# Nixie_Clock_v2.net
KiCad netlist of a schematic drawn in EAGLE
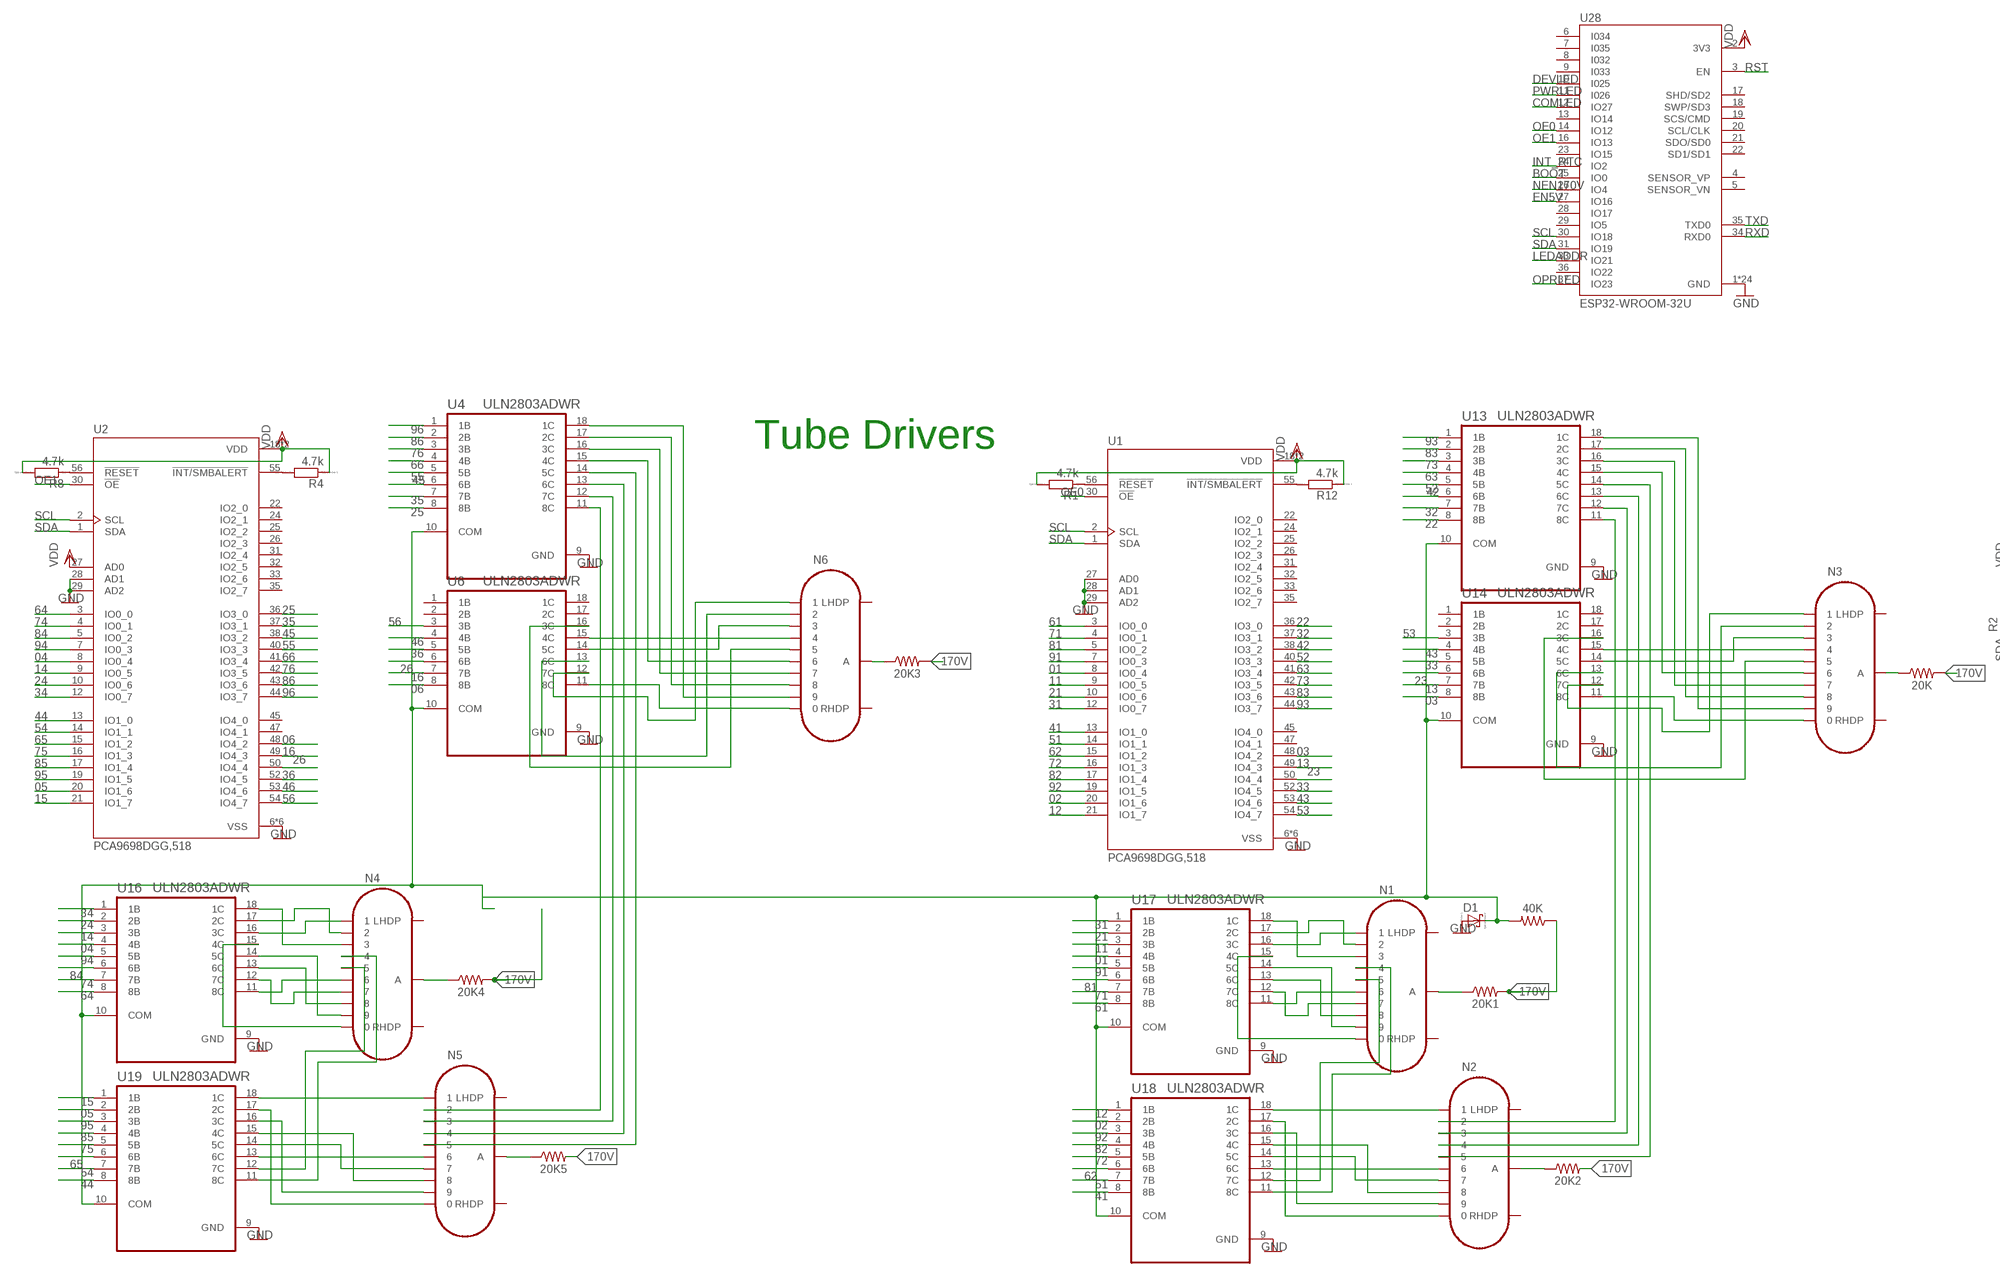
[diagram p0: schematic, sheet 1, part 1 of 2]
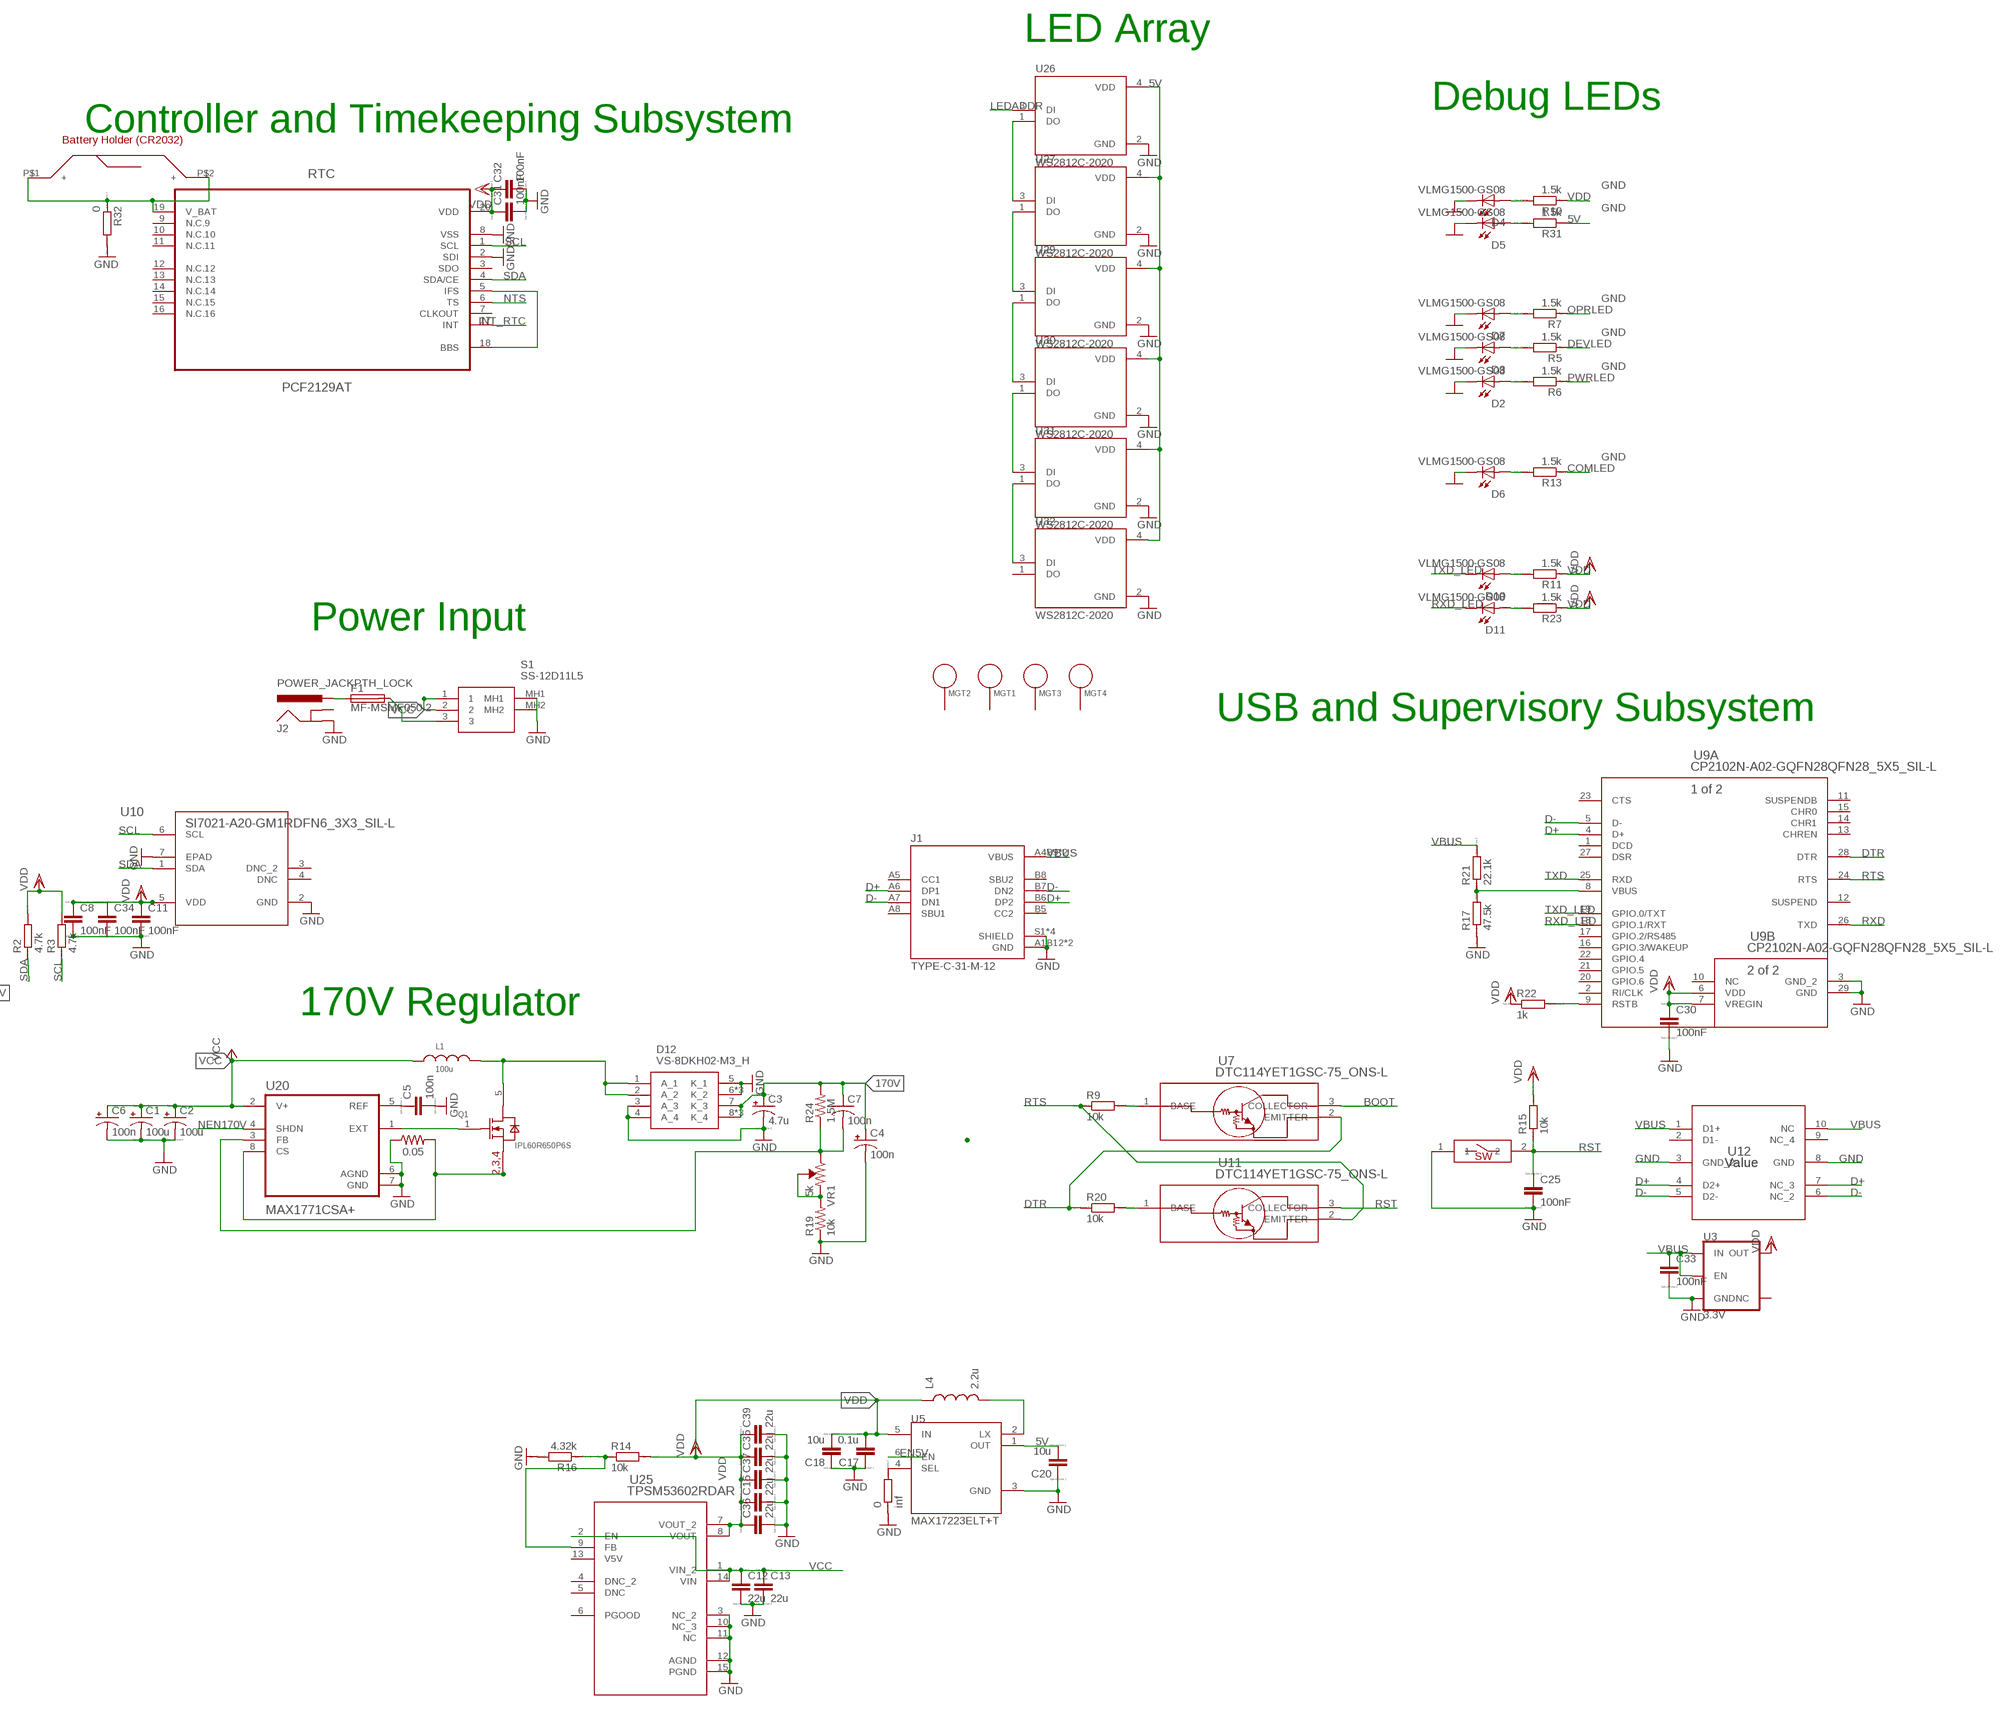
[diagram p1: schematic, sheet 1, part 2 of 2]

(export (version "E")
  (design (tool "Eeschema 10.0.6"))
  (components
    (comp (ref "0")
      (value "inf")
      (footprint "eagle-import:R0402")
      (libsource (lib "eagle-import") (part "RR0402"))
    )
    (comp (ref "0.05")
      (value "0.05")
      (footprint "eagle-import:1210")
      (libsource (lib "eagle-import") (part "0.1OHM-1210-1/2W-1%"))
    )
    (comp (ref "20K")
      (value "0.05")
      (footprint "eagle-import:1210")
      (libsource (lib "eagle-import") (part "0.1OHM-1210-1/2W-1%"))
    )
    (comp (ref "20K1")
      (value "0.05")
      (footprint "eagle-import:1210")
      (libsource (lib "eagle-import") (part "0.1OHM-1210-1/2W-1%"))
    )
    (comp (ref "20K2")
      (value "0.05")
      (footprint "eagle-import:1210")
      (libsource (lib "eagle-import") (part "0.1OHM-1210-1/2W-1%"))
    )
    (comp (ref "20K3")
      (value "0.05")
      (footprint "eagle-import:1210")
      (libsource (lib "eagle-import") (part "0.1OHM-1210-1/2W-1%"))
    )
    (comp (ref "20K4")
      (value "0.05")
      (footprint "eagle-import:1210")
      (libsource (lib "eagle-import") (part "0.1OHM-1210-1/2W-1%"))
    )
    (comp (ref "20K5")
      (value "0.05")
      (footprint "eagle-import:1210")
      (libsource (lib "eagle-import") (part "0.1OHM-1210-1/2W-1%"))
    )
    (comp (ref "40K")
      (value "0.05")
      (footprint "eagle-import:1210")
      (libsource (lib "eagle-import") (part "0.1OHM-1210-1/2W-1%"))
    )
    (comp (ref "C1")
      (value "100u")
      (footprint "eagle-import:E3,5-8")
      (libsource (lib "eagle-import") (part "CPOL-USE3.5-8"))
    )
    (comp (ref "C2")
      (value "100u")
      (footprint "eagle-import:E3,5-8")
      (libsource (lib "eagle-import") (part "CPOL-USE3.5-8"))
    )
    (comp (ref "C3")
      (value "4.7u")
      (footprint "eagle-import:E3,5-8")
      (libsource (lib "eagle-import") (part "CPOL-USE3.5-8"))
    )
    (comp (ref "C4")
      (value "100n")
      (footprint "eagle-import:A_3216-18W")
      (libsource (lib "eagle-import") (part "CAPACITOR-PA/3216-18W"))
    )
    (comp (ref "C5")
      (value "100n")
      (footprint "eagle-import:C0402")
      (libsource (lib "eagle-import") (part "CC0402"))
    )
    (comp (ref "C6")
      (value "100n")
      (footprint "eagle-import:A_3216-18W")
      (libsource (lib "eagle-import") (part "CAPACITOR-PA/3216-18W"))
    )
    (comp (ref "C7")
      (value "100n")
      (footprint "eagle-import:C1206K")
      (libsource (lib "eagle-import") (part "C-USC1206K"))
    )
    (comp (ref "C8")
      (value "100nF")
      (footprint "eagle-import:C0402")
      (libsource (lib "eagle-import") (part "CC0402"))
    )
    (comp (ref "C11")
      (value "100nF")
      (footprint "eagle-import:C0402")
      (libsource (lib "eagle-import") (part "CC0402"))
    )
    (comp (ref "C12")
      (value "22u")
      (footprint "eagle-import:C0603R")
      (libsource (lib "eagle-import") (part "CC0603R"))
    )
    (comp (ref "C13")
      (value "22u")
      (footprint "eagle-import:C0603R")
      (libsource (lib "eagle-import") (part "CC0603R"))
    )
    (comp (ref "C15")
      (value "22u")
      (footprint "eagle-import:C0603R")
      (libsource (lib "eagle-import") (part "CC0603R"))
    )
    (comp (ref "C17")
      (value "0.1u")
      (footprint "eagle-import:C0402")
      (libsource (lib "eagle-import") (part "CC0402"))
    )
    (comp (ref "C18")
      (value "10u")
      (footprint "eagle-import:C0402")
      (libsource (lib "eagle-import") (part "CC0402"))
    )
    (comp (ref "C20")
      (value "10u")
      (footprint "eagle-import:C0402")
      (libsource (lib "eagle-import") (part "CC0402"))
    )
    (comp (ref "C25")
      (value "100nF")
      (footprint "eagle-import:C0402")
      (libsource (lib "eagle-import") (part "CC0402"))
    )
    (comp (ref "C30")
      (value "100nF")
      (footprint "eagle-import:C0402")
      (libsource (lib "eagle-import") (part "CC0402"))
    )
    (comp (ref "C31")
      (value "100nF")
      (footprint "eagle-import:C0402")
      (libsource (lib "eagle-import") (part "CC0402"))
    )
    (comp (ref "C32")
      (value "100nF")
      (footprint "eagle-import:C0402")
      (libsource (lib "eagle-import") (part "CC0402"))
    )
    (comp (ref "C33")
      (value "100nF")
      (footprint "eagle-import:C0402")
      (libsource (lib "eagle-import") (part "CC0402"))
    )
    (comp (ref "C34")
      (value "100nF")
      (footprint "eagle-import:C0402")
      (libsource (lib "eagle-import") (part "CC0402"))
    )
    (comp (ref "C35")
      (value "22u")
      (footprint "eagle-import:C0603R")
      (libsource (lib "eagle-import") (part "CC0603R"))
    )
    (comp (ref "C36")
      (value "22u")
      (footprint "eagle-import:C0603R")
      (libsource (lib "eagle-import") (part "CC0603R"))
    )
    (comp (ref "C37")
      (value "22u")
      (footprint "eagle-import:C0603R")
      (libsource (lib "eagle-import") (part "CC0603R"))
    )
    (comp (ref "C39")
      (value "22u")
      (footprint "eagle-import:C0603R")
      (libsource (lib "eagle-import") (part "CC0603R"))
    )
    (comp (ref "D1")
      (value "SCHOTTKY-DIODE")
      (footprint "eagle-import:DIODE_SMB")
      (libsource (lib "eagle-import") (part "SCHOTTKY-DIODE"))
    )
    (comp (ref "D2")
      (value "VLMG1500-GS08")
      (footprint "eagle-import:LEDC1005X35N")
      (fields (field (name "MF") "Vishay"))
      (libsource (lib "eagle-import") (part "VLMG1500-GS08"))
    )
    (comp (ref "D3")
      (value "VLMG1500-GS08")
      (footprint "eagle-import:LEDC1005X35N")
      (fields (field (name "MF") "Vishay"))
      (libsource (lib "eagle-import") (part "VLMG1500-GS08"))
    )
    (comp (ref "D4")
      (value "VLMG1500-GS08")
      (footprint "eagle-import:LEDC1005X35N")
      (fields (field (name "MF") "Vishay"))
      (libsource (lib "eagle-import") (part "VLMG1500-GS08"))
    )
    (comp (ref "D5")
      (value "VLMG1500-GS08")
      (footprint "eagle-import:LEDC1005X35N")
      (fields (field (name "MF") "Vishay"))
      (libsource (lib "eagle-import") (part "VLMG1500-GS08"))
    )
    (comp (ref "D6")
      (value "VLMG1500-GS08")
      (footprint "eagle-import:LEDC1005X35N")
      (fields (field (name "MF") "Vishay"))
      (libsource (lib "eagle-import") (part "VLMG1500-GS08"))
    )
    (comp (ref "D7")
      (value "VLMG1500-GS08")
      (footprint "eagle-import:LEDC1005X35N")
      (fields (field (name "MF") "Vishay"))
      (libsource (lib "eagle-import") (part "VLMG1500-GS08"))
    )
    (comp (ref "D10")
      (value "VLMG1500-GS08")
      (footprint "eagle-import:LEDC1005X35N")
      (fields (field (name "MF") "Vishay"))
      (libsource (lib "eagle-import") (part "VLMG1500-GS08"))
    )
    (comp (ref "D11")
      (value "VLMG1500-GS08")
      (footprint "eagle-import:LEDC1005X35N")
      (fields (field (name "MF") "Vishay"))
      (libsource (lib "eagle-import") (part "VLMG1500-GS08"))
    )
    (comp (ref "D12")
      (value "VS-8DKH02-M3_H")
      (footprint "eagle-import:VS8DKH02M3H")
      (fields
        (field (name "ARROW_PART_NUMBER") "VS-8DKH02-M3/H")
        (field (name "MOUSER_PART_NUMBER") "78-VS-8DKH02-M3/H")
      )
      (libsource (lib "eagle-import") (part "VS-8DKH02-M3_H"))
    )
    (comp (ref "F1")
      (value "MF-MSMF050-2")
      (footprint "eagle-import:1812")
      (fields
        (field (name "DIGIKEY_PART_NUMBER") "MF-MSMF050-2TR-ND")
        (field (name "MANUFACTURER") "Bourns Inc.")
        (field (name "CREATED_BY") "PCBLayout.com")
      )
      (libsource (lib "eagle-import") (part "MF-MSMF050-2"))
    )
    (comp (ref "J1")
      (value "TYPE-C-31-M-12")
      (footprint "eagle-import:HRO_TYPE-C-31-M-12")
      (fields (field (name "MF") "HRO Electronics Co., Ltd."))
      (libsource (lib "eagle-import") (part "TYPE-C-31-M-12"))
    )
    (comp (ref "J2")
      (value "POWER_JACKPTH_LOCK")
      (footprint "eagle-import:POWER_JACK_PTH_LOCK")
      (libsource (lib "eagle-import") (part "POWER_JACKPTH_LOCK"))
    )
    (comp (ref "L1")
      (value "100u")
      (footprint "eagle-import:WE-PD_1260_1245_1280_1210")
      (libsource (lib "eagle-import") (part "WE-PD_1210_7447709001"))
    )
    (comp (ref "L4")
      (value "2.2u")
      (footprint "eagle-import:L0603")
      (libsource (lib "eagle-import") (part "INDUCTOR"))
    )
    (comp (ref "MGT1")
      (value "BEAGLEBONEBLACK_MOUNTING_HOLE")
      (footprint "eagle-import:BEAGLEBONEBLACK_MOUNTING_HOLE")
      (libsource (lib "eagle-import") (part "BEAGLEBONEBLACK_MOUNTING_HOLE"))
    )
    (comp (ref "MGT2")
      (value "BEAGLEBONEBLACK_MOUNTING_HOLE")
      (footprint "eagle-import:BEAGLEBONEBLACK_MOUNTING_HOLE")
      (libsource (lib "eagle-import") (part "BEAGLEBONEBLACK_MOUNTING_HOLE"))
    )
    (comp (ref "MGT3")
      (value "BEAGLEBONEBLACK_MOUNTING_HOLE")
      (footprint "eagle-import:BEAGLEBONEBLACK_MOUNTING_HOLE")
      (libsource (lib "eagle-import") (part "BEAGLEBONEBLACK_MOUNTING_HOLE"))
    )
    (comp (ref "MGT4")
      (value "BEAGLEBONEBLACK_MOUNTING_HOLE")
      (footprint "eagle-import:BEAGLEBONEBLACK_MOUNTING_HOLE")
      (libsource (lib "eagle-import") (part "BEAGLEBONEBLACK_MOUNTING_HOLE"))
    )
    (comp (ref "N1")
      (value "IN-14")
      (footprint "eagle-import:IN-14")
      (libsource (lib "eagle-import") (part "IN-14"))
    )
    (comp (ref "N2")
      (value "IN-14")
      (footprint "eagle-import:IN-14")
      (libsource (lib "eagle-import") (part "IN-14"))
    )
    (comp (ref "N3")
      (value "IN-14")
      (footprint "eagle-import:IN-14")
      (libsource (lib "eagle-import") (part "IN-14"))
    )
    (comp (ref "N4")
      (value "IN-14")
      (footprint "eagle-import:IN-14")
      (libsource (lib "eagle-import") (part "IN-14"))
    )
    (comp (ref "N5")
      (value "IN-14")
      (footprint "eagle-import:IN-14")
      (libsource (lib "eagle-import") (part "IN-14"))
    )
    (comp (ref "N6")
      (value "IN-14")
      (footprint "eagle-import:IN-14")
      (libsource (lib "eagle-import") (part "IN-14"))
    )
    (comp (ref "Q1")
      (value "IPL60R650P6S")
      (footprint "eagle-import:INF-PG-TSON-8-2")
      (libsource (lib "eagle-import") (part "IPL60R650P6S"))
    )
    (comp (ref "R1")
      (value "4.7k")
      (footprint "eagle-import:R0402")
      (libsource (lib "eagle-import") (part "RR0402"))
    )
    (comp (ref "R2")
      (value "4.7k")
      (footprint "eagle-import:R0402")
      (libsource (lib "eagle-import") (part "RR0402"))
    )
    (comp (ref "R3")
      (value "4.7k")
      (footprint "eagle-import:R0402")
      (libsource (lib "eagle-import") (part "RR0402"))
    )
    (comp (ref "R4")
      (value "4.7k")
      (footprint "eagle-import:R0402")
      (libsource (lib "eagle-import") (part "RR0402"))
    )
    (comp (ref "R5")
      (value "1.5k")
      (footprint "eagle-import:R0402")
      (libsource (lib "eagle-import") (part "RR0402"))
    )
    (comp (ref "R6")
      (value "1.5k")
      (footprint "eagle-import:R0402")
      (libsource (lib "eagle-import") (part "RR0402"))
    )
    (comp (ref "R7")
      (value "1.5k")
      (footprint "eagle-import:R0402")
      (libsource (lib "eagle-import") (part "RR0402"))
    )
    (comp (ref "R8")
      (value "4.7k")
      (footprint "eagle-import:R0402")
      (libsource (lib "eagle-import") (part "RR0402"))
    )
    (comp (ref "R9")
      (value "10k")
      (footprint "eagle-import:R0402")
      (libsource (lib "eagle-import") (part "RR0402"))
    )
    (comp (ref "R10")
      (value "1.5k")
      (footprint "eagle-import:R0402")
      (libsource (lib "eagle-import") (part "RR0402"))
    )
    (comp (ref "R11")
      (value "1.5k")
      (footprint "eagle-import:R0402")
      (libsource (lib "eagle-import") (part "RR0402"))
    )
    (comp (ref "R12")
      (value "4.7k")
      (footprint "eagle-import:R0402")
      (libsource (lib "eagle-import") (part "RR0402"))
    )
    (comp (ref "R13")
      (value "1.5k")
      (footprint "eagle-import:R0402")
      (libsource (lib "eagle-import") (part "RR0402"))
    )
    (comp (ref "R14")
      (value "10k")
      (footprint "eagle-import:R0402")
      (libsource (lib "eagle-import") (part "RR0402"))
    )
    (comp (ref "R15")
      (value "10k")
      (footprint "eagle-import:R0402")
      (libsource (lib "eagle-import") (part "RR0402"))
    )
    (comp (ref "R16")
      (value "4.32k")
      (footprint "eagle-import:R0402")
      (libsource (lib "eagle-import") (part "RR0402"))
    )
    (comp (ref "R17")
      (value "47.5k")
      (footprint "eagle-import:R0402")
      (libsource (lib "eagle-import") (part "RR0402"))
    )
    (comp (ref "R19")
      (value "10k")
      (footprint "eagle-import:M1206")
      (libsource (lib "eagle-import") (part "R-US_M1206"))
    )
    (comp (ref "R20")
      (value "10k")
      (footprint "eagle-import:R0402")
      (libsource (lib "eagle-import") (part "RR0402"))
    )
    (comp (ref "R21")
      (value "22.1k")
      (footprint "eagle-import:R0402")
      (libsource (lib "eagle-import") (part "RR0402"))
    )
    (comp (ref "R22")
      (value "1k")
      (footprint "eagle-import:R0402")
      (libsource (lib "eagle-import") (part "RR0402"))
    )
    (comp (ref "R23")
      (value "1.5k")
      (footprint "eagle-import:R0402")
      (libsource (lib "eagle-import") (part "RR0402"))
    )
    (comp (ref "R24")
      (value "1.5M")
      (footprint "eagle-import:M1206")
      (libsource (lib "eagle-import") (part "R-US_M1206"))
    )
    (comp (ref "R31")
      (value "1.5k")
      (footprint "eagle-import:R0402")
      (libsource (lib "eagle-import") (part "RR0402"))
    )
    (comp (ref "R32")
      (value "0")
      (footprint "eagle-import:R0402")
      (libsource (lib "eagle-import") (part "RR0402"))
    )
    (comp (ref "RESET")
      (value "SMDSWITCH")
      (footprint "eagle-import:RESC4217X170")
      (libsource (lib "eagle-import") (part "SMDSWITCH"))
    )
    (comp (ref "S1")
      (value "SS-12D11L5")
      (footprint "eagle-import:SS12D11L5")
      (libsource (lib "eagle-import") (part "SS-12D11L5"))
    )
    (comp (ref "U$1")
      (value "PCF2129AT")
      (footprint "eagle-import:PCF2129AT")
      (libsource (lib "eagle-import") (part "PCF2129AT"))
    )
    (comp (ref "U$2")
      (value "HOLDER")
      (footprint "eagle-import:HOLDER")
      (libsource (lib "eagle-import") (part "HOLDER"))
    )
    (comp (ref "U1")
      (value "PCA9698DGG,518")
      (footprint "eagle-import:SOP50P810X120-56N")
      (fields (field (name "MF") "NXP USA"))
      (libsource (lib "eagle-import") (part "PCA9698DGG,518"))
    )
    (comp (ref "U2")
      (value "PCA9698DGG,518")
      (footprint "eagle-import:SOP50P810X120-56N")
      (fields (field (name "MF") "NXP USA"))
      (libsource (lib "eagle-import") (part "PCA9698DGG,518"))
    )
    (comp (ref "U3")
      (value "3.3V")
      (footprint "eagle-import:SOT23-5")
      (libsource (lib "eagle-import") (part "V_REG_AP2112K-3.3V"))
    )
    (comp (ref "U4")
      (value "ULN2803ADWR")
      (footprint "eagle-import:SOIC127P1030X265-18N")
      (fields (field (name "MF") "Texas Instruments"))
      (libsource (lib "eagle-import") (part "ULN2803ADWR"))
    )
    (comp (ref "U5")
      (value "MAX17223ELT+T")
      (footprint "eagle-import:PSON65P200X200X80-6N")
      (fields (field (name "MF") "Maxim Integrated") (field (name "MP") "MAX17223ELT+"))
      (libsource (lib "eagle-import") (part "MAX17223ELT+T"))
    )
    (comp (ref "U6")
      (value "ULN2803ADWR")
      (footprint "eagle-import:SOIC127P1030X265-18N")
      (fields (field (name "MF") "Texas Instruments"))
      (libsource (lib "eagle-import") (part "ULN2803ADWR"))
    )
    (comp (ref "U7")
      (value "DTC114YET1GSC-75_ONS-L")
      (footprint "eagle-import:SC-75_ONS-L")
      (fields
        (field (name "MANUFACTURER_PART_NUMBER") "DTC114YET1G")
        (field (name "COPYRIGHT") "Copyright (C) 2018 Accelerated Designs. All rights reserved")
      )
      (libsource (lib "eagle-import") (part "DTC114YET1GSC-75_ONS-L"))
    )
    (comp (ref "U9")
      (value "CP2102N-A02-GQFN28QFN28_5X5_SIL-L")
      (footprint "eagle-import:QFN28_5X5_SIL-L")
      (fields
        (field (name "MANUFACTURER_PART_NUMBER") "CP2102N-A02-GQFN28")
        (field (name "COPYRIGHT") "Copyright (C) 2018 Accelerated Designs. All rights reserved")
      )
      (libsource (lib "eagle-import") (part "CP2102N-A02-GQFN28QFN28_5X5_SIL-L"))
    )
    (comp (ref "U10")
      (value "SI7021-A20-GM1RDFN6_3X3_SIL-L")
      (footprint "eagle-import:DFN6_3X3_SIL-L")
      (fields
        (field (name "MANUFACTURER_PART_NUMBER") "SI7021-A20-GM1R")
        (field (name "COPYRIGHT") "Copyright (C) 2018 Accelerated Designs. All rights reserved")
      )
      (libsource (lib "eagle-import") (part "SI7021-A20-GM1RDFN6_3X3_SIL-L"))
    )
    (comp (ref "U11")
      (value "DTC114YET1GSC-75_ONS-L")
      (footprint "eagle-import:SC-75_ONS-L")
      (fields
        (field (name "MANUFACTURER_PART_NUMBER") "DTC114YET1G")
        (field (name "COPYRIGHT") "Copyright (C) 2018 Accelerated Designs. All rights reserved")
      )
      (libsource (lib "eagle-import") (part "DTC114YET1GSC-75_ONS-L"))
    )
    (comp (ref "U12")
      (value "Value")
      (footprint "eagle-import:DQA0010A")
      (fields (field (name "MANUFACTURER") "Texas Instruments") (field (name "PARTNUMBER") "ESD204DQAR"))
      (libsource (lib "eagle-import") (part "ESD204DQAR"))
    )
    (comp (ref "U13")
      (value "ULN2803ADWR")
      (footprint "eagle-import:SOIC127P1030X265-18N")
      (fields (field (name "MF") "Texas Instruments"))
      (libsource (lib "eagle-import") (part "ULN2803ADWR"))
    )
    (comp (ref "U14")
      (value "ULN2803ADWR")
      (footprint "eagle-import:SOIC127P1030X265-18N")
      (fields (field (name "MF") "Texas Instruments"))
      (libsource (lib "eagle-import") (part "ULN2803ADWR"))
    )
    (comp (ref "U16")
      (value "ULN2803ADWR")
      (footprint "eagle-import:SOIC127P1030X265-18N")
      (fields (field (name "MF") "Texas Instruments"))
      (libsource (lib "eagle-import") (part "ULN2803ADWR"))
    )
    (comp (ref "U17")
      (value "ULN2803ADWR")
      (footprint "eagle-import:SOIC127P1030X265-18N")
      (fields (field (name "MF") "Texas Instruments"))
      (libsource (lib "eagle-import") (part "ULN2803ADWR"))
    )
    (comp (ref "U18")
      (value "ULN2803ADWR")
      (footprint "eagle-import:SOIC127P1030X265-18N")
      (fields (field (name "MF") "Texas Instruments"))
      (libsource (lib "eagle-import") (part "ULN2803ADWR"))
    )
    (comp (ref "U19")
      (value "ULN2803ADWR")
      (footprint "eagle-import:SOIC127P1030X265-18N")
      (fields (field (name "MF") "Texas Instruments"))
      (libsource (lib "eagle-import") (part "ULN2803ADWR"))
    )
    (comp (ref "U20")
      (value "MAX1771CSA+")
      (footprint "eagle-import:SOIC127P600X175-8N")
      (fields (field (name "MF") "Maxim Integrated"))
      (libsource (lib "eagle-import") (part "MAX1771CSA+"))
    )
    (comp (ref "U25")
      (value "TPSM53602RDAR")
      (footprint "eagle-import:B3QFN15_RDA_TEX")
      (fields (field (name "COPYRIGHT") "Copyright (C) 2018 Accelerated Designs. All rights reserved"))
      (libsource (lib "eagle-import") (part "TPSM53602RDAR"))
    )
    (comp (ref "U26")
      (value "WS2812C-2020")
      (footprint "eagle-import:LED_WS2812C-2020")
      (fields (field (name "MF") "Worldsemi"))
      (libsource (lib "eagle-import") (part "WS2812C-2020"))
    )
    (comp (ref "U27")
      (value "WS2812C-2020")
      (footprint "eagle-import:LED_WS2812C-2020")
      (fields (field (name "MF") "Worldsemi"))
      (libsource (lib "eagle-import") (part "WS2812C-2020"))
    )
    (comp (ref "U28")
      (value "ESP32-WROOM-32U")
      (footprint "eagle-import:XCVR_ESP32-WROOM-32U")
      (fields (field (name "MF") "Espressif Systems"))
      (libsource (lib "eagle-import") (part "ESP32-WROOM-32U"))
    )
    (comp (ref "U29")
      (value "WS2812C-2020")
      (footprint "eagle-import:LED_WS2812C-2020")
      (fields (field (name "MF") "Worldsemi"))
      (libsource (lib "eagle-import") (part "WS2812C-2020"))
    )
    (comp (ref "U30")
      (value "WS2812C-2020")
      (footprint "eagle-import:LED_WS2812C-2020")
      (fields (field (name "MF") "Worldsemi"))
      (libsource (lib "eagle-import") (part "WS2812C-2020"))
    )
    (comp (ref "U31")
      (value "WS2812C-2020")
      (footprint "eagle-import:LED_WS2812C-2020")
      (fields (field (name "MF") "Worldsemi"))
      (libsource (lib "eagle-import") (part "WS2812C-2020"))
    )
    (comp (ref "U32")
      (value "WS2812C-2020")
      (footprint "eagle-import:LED_WS2812C-2020")
      (fields (field (name "MF") "Worldsemi"))
      (libsource (lib "eagle-import") (part "WS2812C-2020"))
    )
    (comp (ref "VR1")
      (value "5k")
      (footprint "eagle-import:TRIMPOT-SMD-3MM-CLOSED")
      (libsource (lib "eagle-import") (part "TRIMPOT-SMD-3MM-CLOSED-1/8W-20%"))
    )
  )
  (nets
    (net (code "1") (name "/01") (class "Default")
      (node (ref "U1") (pin "8") (pinfunction "IO0_4_8") (pintype "bidirectional"))
      (node (ref "U17") (pin "4") (pinfunction "4B_4") (pintype "input"))
    )
    (net (code "2") (name "/02") (class "Default")
      (node (ref "U1") (pin "20") (pinfunction "IO1_6_20") (pintype "bidirectional"))
      (node (ref "U18") (pin "2") (pinfunction "2B_2") (pintype "input"))
    )
    (net (code "3") (name "/03") (class "Default")
      (node (ref "U1") (pin "48") (pinfunction "IO4_2_48") (pintype "bidirectional"))
      (node (ref "U14") (pin "8") (pinfunction "8B_8") (pintype "input"))
    )
    (net (code "4") (name "/04") (class "Default")
      (node (ref "U16") (pin "4") (pinfunction "4B_4") (pintype "input"))
      (node (ref "U2") (pin "8") (pinfunction "IO0_4_8") (pintype "bidirectional"))
    )
    (net (code "5") (name "/05") (class "Default")
      (node (ref "U19") (pin "2") (pinfunction "2B_2") (pintype "input"))
      (node (ref "U2") (pin "20") (pinfunction "IO1_6_20") (pintype "bidirectional"))
    )
    (net (code "6") (name "/5V") (class "Default")
      (node (ref "C20") (pin "2") (pinfunction "2_2") (pintype "passive"))
      (node (ref "R31") (pin "1") (pinfunction "1_1") (pintype "passive"))
      (node (ref "U26") (pin "4") (pinfunction "VDD_4") (pintype "power_in"))
      (node (ref "U27") (pin "4") (pinfunction "VDD_4") (pintype "power_in"))
      (node (ref "U29") (pin "4") (pinfunction "VDD_4") (pintype "power_in"))
      (node (ref "U30") (pin "4") (pinfunction "VDD_4") (pintype "power_in"))
      (node (ref "U31") (pin "4") (pinfunction "VDD_4") (pintype "power_in"))
      (node (ref "U32") (pin "4") (pinfunction "VDD_4") (pintype "power_in"))
      (node (ref "U5") (pin "1") (pinfunction "OUT_1") (pintype "output"))
    )
    (net (code "7") (name "/06") (class "Default")
      (node (ref "U2") (pin "48") (pinfunction "IO4_2_48") (pintype "bidirectional"))
      (node (ref "U6") (pin "8") (pinfunction "8B_8") (pintype "input"))
    )
    (net (code "8") (name "/11") (class "Default")
      (node (ref "U1") (pin "9") (pinfunction "IO0_5_9") (pintype "bidirectional"))
      (node (ref "U17") (pin "3") (pinfunction "3B_3") (pintype "input"))
    )
    (net (code "9") (name "/12") (class "Default")
      (node (ref "U1") (pin "21") (pinfunction "IO1_7_21") (pintype "bidirectional"))
      (node (ref "U18") (pin "1") (pinfunction "1B_1") (pintype "input"))
    )
    (net (code "10") (name "/13") (class "Default")
      (node (ref "U1") (pin "49") (pinfunction "IO4_3_49") (pintype "bidirectional"))
      (node (ref "U14") (pin "7") (pinfunction "7B_7") (pintype "input"))
    )
    (net (code "11") (name "/14") (class "Default")
      (node (ref "U16") (pin "3") (pinfunction "3B_3") (pintype "input"))
      (node (ref "U2") (pin "9") (pinfunction "IO0_5_9") (pintype "bidirectional"))
    )
    (net (code "12") (name "/15") (class "Default")
      (node (ref "U19") (pin "1") (pinfunction "1B_1") (pintype "input"))
      (node (ref "U2") (pin "21") (pinfunction "IO1_7_21") (pintype "bidirectional"))
    )
    (net (code "13") (name "/16") (class "Default")
      (node (ref "U2") (pin "49") (pinfunction "IO4_3_49") (pintype "bidirectional"))
      (node (ref "U6") (pin "7") (pinfunction "7B_7") (pintype "input"))
    )
    (net (code "14") (name "/21") (class "Default")
      (node (ref "U1") (pin "10") (pinfunction "IO0_6_10") (pintype "bidirectional"))
      (node (ref "U17") (pin "2") (pinfunction "2B_2") (pintype "input"))
    )
    (net (code "15") (name "/22") (class "Default")
      (node (ref "U1") (pin "36") (pinfunction "IO3_0_36") (pintype "bidirectional"))
      (node (ref "U13") (pin "8") (pinfunction "8B_8") (pintype "input"))
    )
    (net (code "16") (name "/23") (class "Default")
      (node (ref "U1") (pin "50") (pinfunction "IO4_4_50") (pintype "bidirectional"))
      (node (ref "U14") (pin "6") (pinfunction "6B_6") (pintype "input"))
    )
    (net (code "17") (name "/24") (class "Default")
      (node (ref "U16") (pin "2") (pinfunction "2B_2") (pintype "input"))
      (node (ref "U2") (pin "10") (pinfunction "IO0_6_10") (pintype "bidirectional"))
    )
    (net (code "18") (name "/25") (class "Default")
      (node (ref "U2") (pin "36") (pinfunction "IO3_0_36") (pintype "bidirectional"))
      (node (ref "U4") (pin "8") (pinfunction "8B_8") (pintype "input"))
    )
    (net (code "19") (name "/26") (class "Default")
      (node (ref "U2") (pin "50") (pinfunction "IO4_4_50") (pintype "bidirectional"))
      (node (ref "U6") (pin "6") (pinfunction "6B_6") (pintype "input"))
    )
    (net (code "20") (name "/31") (class "Default")
      (node (ref "U1") (pin "12") (pinfunction "IO0_7_12") (pintype "bidirectional"))
      (node (ref "U17") (pin "1") (pinfunction "1B_1") (pintype "input"))
    )
    (net (code "21") (name "/32") (class "Default")
      (node (ref "U1") (pin "37") (pinfunction "IO3_1_37") (pintype "bidirectional"))
      (node (ref "U13") (pin "7") (pinfunction "7B_7") (pintype "input"))
    )
    (net (code "22") (name "/33") (class "Default")
      (node (ref "U1") (pin "52") (pinfunction "IO4_5_52") (pintype "bidirectional"))
      (node (ref "U14") (pin "5") (pinfunction "5B_5") (pintype "input"))
    )
    (net (code "23") (name "/34") (class "Default")
      (node (ref "U16") (pin "1") (pinfunction "1B_1") (pintype "input"))
      (node (ref "U2") (pin "12") (pinfunction "IO0_7_12") (pintype "bidirectional"))
    )
    (net (code "24") (name "/35") (class "Default")
      (node (ref "U2") (pin "37") (pinfunction "IO3_1_37") (pintype "bidirectional"))
      (node (ref "U4") (pin "7") (pinfunction "7B_7") (pintype "input"))
    )
    (net (code "25") (name "/36") (class "Default")
      (node (ref "U2") (pin "52") (pinfunction "IO4_5_52") (pintype "bidirectional"))
      (node (ref "U6") (pin "5") (pinfunction "5B_5") (pintype "input"))
    )
    (net (code "26") (name "/41") (class "Default")
      (node (ref "U1") (pin "13") (pinfunction "IO1_0_13") (pintype "bidirectional"))
      (node (ref "U18") (pin "8") (pinfunction "8B_8") (pintype "input"))
    )
    (net (code "27") (name "/42") (class "Default")
      (node (ref "U1") (pin "38") (pinfunction "IO3_2_38") (pintype "bidirectional"))
      (node (ref "U13") (pin "6") (pinfunction "6B_6") (pintype "input"))
    )
    (net (code "28") (name "/43") (class "Default")
      (node (ref "U1") (pin "53") (pinfunction "IO4_6_53") (pintype "bidirectional"))
      (node (ref "U14") (pin "4") (pinfunction "4B_4") (pintype "input"))
    )
    (net (code "29") (name "/44") (class "Default")
      (node (ref "U19") (pin "8") (pinfunction "8B_8") (pintype "input"))
      (node (ref "U2") (pin "13") (pinfunction "IO1_0_13") (pintype "bidirectional"))
    )
    (net (code "30") (name "/45") (class "Default")
      (node (ref "U2") (pin "38") (pinfunction "IO3_2_38") (pintype "bidirectional"))
      (node (ref "U4") (pin "6") (pinfunction "6B_6") (pintype "input"))
    )
    (net (code "31") (name "/46") (class "Default")
      (node (ref "U2") (pin "53") (pinfunction "IO4_6_53") (pintype "bidirectional"))
      (node (ref "U6") (pin "4") (pinfunction "4B_4") (pintype "input"))
    )
    (net (code "32") (name "/51") (class "Default")
      (node (ref "U1") (pin "14") (pinfunction "IO1_1_14") (pintype "bidirectional"))
      (node (ref "U18") (pin "7") (pinfunction "7B_7") (pintype "input"))
    )
    (net (code "33") (name "/52") (class "Default")
      (node (ref "U1") (pin "40") (pinfunction "IO3_3_40") (pintype "bidirectional"))
      (node (ref "U13") (pin "5") (pinfunction "5B_5") (pintype "input"))
    )
    (net (code "34") (name "/53") (class "Default")
      (node (ref "U1") (pin "54") (pinfunction "IO4_7_54") (pintype "bidirectional"))
      (node (ref "U14") (pin "3") (pinfunction "3B_3") (pintype "input"))
    )
    (net (code "35") (name "/54") (class "Default")
      (node (ref "U19") (pin "7") (pinfunction "7B_7") (pintype "input"))
      (node (ref "U2") (pin "14") (pinfunction "IO1_1_14") (pintype "bidirectional"))
    )
    (net (code "36") (name "/55") (class "Default")
      (node (ref "U2") (pin "40") (pinfunction "IO3_3_40") (pintype "bidirectional"))
      (node (ref "U4") (pin "5") (pinfunction "5B_5") (pintype "input"))
    )
    (net (code "37") (name "/56") (class "Default")
      (node (ref "U2") (pin "54") (pinfunction "IO4_7_54") (pintype "bidirectional"))
      (node (ref "U6") (pin "3") (pinfunction "3B_3") (pintype "input"))
    )
    (net (code "38") (name "/61") (class "Default")
      (node (ref "U1") (pin "3") (pinfunction "IO0_0_3") (pintype "bidirectional"))
      (node (ref "U17") (pin "8") (pinfunction "8B_8") (pintype "input"))
    )
    (net (code "39") (name "/62") (class "Default")
      (node (ref "U1") (pin "15") (pinfunction "IO1_2_15") (pintype "bidirectional"))
      (node (ref "U18") (pin "6") (pinfunction "6B_6") (pintype "input"))
    )
    (net (code "40") (name "/63") (class "Default")
      (node (ref "U1") (pin "41") (pinfunction "IO3_4_41") (pintype "bidirectional"))
      (node (ref "U13") (pin "4") (pinfunction "4B_4") (pintype "input"))
    )
    (net (code "41") (name "/64") (class "Default")
      (node (ref "U16") (pin "8") (pinfunction "8B_8") (pintype "input"))
      (node (ref "U2") (pin "3") (pinfunction "IO0_0_3") (pintype "bidirectional"))
    )
    (net (code "42") (name "/65") (class "Default")
      (node (ref "U19") (pin "6") (pinfunction "6B_6") (pintype "input"))
      (node (ref "U2") (pin "15") (pinfunction "IO1_2_15") (pintype "bidirectional"))
    )
    (net (code "43") (name "/66") (class "Default")
      (node (ref "U2") (pin "41") (pinfunction "IO3_4_41") (pintype "bidirectional"))
      (node (ref "U4") (pin "4") (pinfunction "4B_4") (pintype "input"))
    )
    (net (code "44") (name "/71") (class "Default")
      (node (ref "U1") (pin "4") (pinfunction "IO0_1_4") (pintype "bidirectional"))
      (node (ref "U17") (pin "7") (pinfunction "7B_7") (pintype "input"))
    )
    (net (code "45") (name "/72") (class "Default")
      (node (ref "U1") (pin "16") (pinfunction "IO1_3_16") (pintype "bidirectional"))
      (node (ref "U18") (pin "5") (pinfunction "5B_5") (pintype "input"))
    )
    (net (code "46") (name "/73") (class "Default")
      (node (ref "U1") (pin "42") (pinfunction "IO3_5_42") (pintype "bidirectional"))
      (node (ref "U13") (pin "3") (pinfunction "3B_3") (pintype "input"))
    )
    (net (code "47") (name "/74") (class "Default")
      (node (ref "U16") (pin "7") (pinfunction "7B_7") (pintype "input"))
      (node (ref "U2") (pin "4") (pinfunction "IO0_1_4") (pintype "bidirectional"))
    )
    (net (code "48") (name "/75") (class "Default")
      (node (ref "U19") (pin "5") (pinfunction "5B_5") (pintype "input"))
      (node (ref "U2") (pin "16") (pinfunction "IO1_3_16") (pintype "bidirectional"))
    )
    (net (code "49") (name "/76") (class "Default")
      (node (ref "U2") (pin "42") (pinfunction "IO3_5_42") (pintype "bidirectional"))
      (node (ref "U4") (pin "3") (pinfunction "3B_3") (pintype "input"))
    )
    (net (code "50") (name "/81") (class "Default")
      (node (ref "U1") (pin "5") (pinfunction "IO0_2_5") (pintype "bidirectional"))
      (node (ref "U17") (pin "6") (pinfunction "6B_6") (pintype "input"))
    )
    (net (code "51") (name "/82") (class "Default")
      (node (ref "U1") (pin "17") (pinfunction "IO1_4_17") (pintype "bidirectional"))
      (node (ref "U18") (pin "4") (pinfunction "4B_4") (pintype "input"))
    )
    (net (code "52") (name "/83") (class "Default")
      (node (ref "U1") (pin "43") (pinfunction "IO3_6_43") (pintype "bidirectional"))
      (node (ref "U13") (pin "2") (pinfunction "2B_2") (pintype "input"))
    )
    (net (code "53") (name "/84") (class "Default")
      (node (ref "U16") (pin "6") (pinfunction "6B_6") (pintype "input"))
      (node (ref "U2") (pin "5") (pinfunction "IO0_2_5") (pintype "bidirectional"))
    )
    (net (code "54") (name "/85") (class "Default")
      (node (ref "U19") (pin "4") (pinfunction "4B_4") (pintype "input"))
      (node (ref "U2") (pin "17") (pinfunction "IO1_4_17") (pintype "bidirectional"))
    )
    (net (code "55") (name "/86") (class "Default")
      (node (ref "U2") (pin "43") (pinfunction "IO3_6_43") (pintype "bidirectional"))
      (node (ref "U4") (pin "2") (pinfunction "2B_2") (pintype "input"))
    )
    (net (code "56") (name "/91") (class "Default")
      (node (ref "U1") (pin "7") (pinfunction "IO0_3_7") (pintype "bidirectional"))
      (node (ref "U17") (pin "5") (pinfunction "5B_5") (pintype "input"))
    )
    (net (code "57") (name "/92") (class "Default")
      (node (ref "U1") (pin "19") (pinfunction "IO1_5_19") (pintype "bidirectional"))
      (node (ref "U18") (pin "3") (pinfunction "3B_3") (pintype "input"))
    )
    (net (code "58") (name "/93") (class "Default")
      (node (ref "U1") (pin "44") (pinfunction "IO3_7_44") (pintype "bidirectional"))
      (node (ref "U13") (pin "1") (pinfunction "1B_1") (pintype "input"))
    )
    (net (code "59") (name "/94") (class "Default")
      (node (ref "U16") (pin "5") (pinfunction "5B_5") (pintype "input"))
      (node (ref "U2") (pin "7") (pinfunction "IO0_3_7") (pintype "bidirectional"))
    )
    (net (code "60") (name "/95") (class "Default")
      (node (ref "U19") (pin "3") (pinfunction "3B_3") (pintype "input"))
      (node (ref "U2") (pin "19") (pinfunction "IO1_5_19") (pintype "bidirectional"))
    )
    (net (code "61") (name "/96") (class "Default")
      (node (ref "U2") (pin "44") (pinfunction "IO3_7_44") (pintype "bidirectional"))
      (node (ref "U4") (pin "1") (pinfunction "1B_1") (pintype "input"))
    )
    (net (code "62") (name "/BOOT") (class "Default")
      (node (ref "U28") (pin "25") (pinfunction "IO0_25") (pintype "bidirectional"))
      (node (ref "U7") (pin "3") (pinfunction "COLLECTOR_3") (pintype "output"))
    )
    (net (code "63") (name "/COMLED") (class "Default")
      (node (ref "R13") (pin "1") (pinfunction "1_1") (pintype "passive"))
      (node (ref "U28") (pin "12") (pinfunction "IO27_12") (pintype "bidirectional"))
    )
    (net (code "64") (name "/D+") (class "Default")
      (node (ref "J1") (pin "A6") (pinfunction "DP1_A6") (pintype "bidirectional"))
      (node (ref "J1") (pin "B6") (pinfunction "DP2_B6") (pintype "bidirectional"))
      (node (ref "U12") (pin "4") (pinfunction "D2+_4") (pintype "bidirectional"))
      (node (ref "U12") (pin "7") (pinfunction "NC_3_7") (pintype "passive"))
      (node (ref "U9") (pin "4") (pinfunction "D+_4") (pintype "input"))
    )
    (net (code "65") (name "/D-") (class "Default")
      (node (ref "J1") (pin "A7") (pinfunction "DN1_A7") (pintype "bidirectional"))
      (node (ref "J1") (pin "B7") (pinfunction "DN2_B7") (pintype "bidirectional"))
      (node (ref "U12") (pin "5") (pinfunction "D2-_5") (pintype "bidirectional"))
      (node (ref "U12") (pin "6") (pinfunction "NC_2_6") (pintype "passive"))
      (node (ref "U9") (pin "5") (pinfunction "D-_5") (pintype "input"))
    )
    (net (code "66") (name "/DEVLED") (class "Default")
      (node (ref "R5") (pin "1") (pinfunction "1_1") (pintype "passive"))
      (node (ref "U28") (pin "10") (pinfunction "I025_10") (pintype "bidirectional"))
    )
    (net (code "67") (name "/DTR") (class "Default")
      (node (ref "R20") (pin "1") (pinfunction "1_1") (pintype "passive"))
      (node (ref "U7") (pin "2") (pinfunction "EMITTER_2") (pintype "passive"))
      (node (ref "U9") (pin "28") (pinfunction "DTR_28") (pintype "output"))
    )
    (net (code "68") (name "/EN5V") (class "Default")
      (node (ref "U28") (pin "27") (pinfunction "IO16_27") (pintype "bidirectional"))
      (node (ref "U5") (pin "6") (pinfunction "EN_6") (pintype "input"))
    )
    (net (code "69") (name "/INT_RTC") (class "Default")
      (node (ref "U$1") (pin "17") (pinfunction "INT_17") (pintype "output"))
      (node (ref "U28") (pin "24") (pinfunction "IO2_24") (pintype "bidirectional"))
    )
    (net (code "70") (name "/LEDADDR") (class "Default")
      (node (ref "U26") (pin "3") (pinfunction "DI_3") (pintype "input"))
      (node (ref "U28") (pin "33") (pinfunction "IO21_33") (pintype "bidirectional"))
    )
    (net (code "71") (name "/NEN170V") (class "Default")
      (node (ref "U20") (pin "4") (pinfunction "SHDN_4") (pintype "input"))
      (node (ref "U28") (pin "26") (pinfunction "IO4_26") (pintype "bidirectional"))
    )
    (net (code "72") (name "/NTS") (class "Default")
      (node (ref "U$1") (pin "6") (pinfunction "TS_6") (pintype "input"))
    )
    (net (code "73") (name "/OE0") (class "Default")
      (node (ref "U1") (pin "30") (pinfunction "~{OE}_30") (pintype "input"))
      (node (ref "U28") (pin "14") (pinfunction "IO12_14") (pintype "bidirectional"))
    )
    (net (code "74") (name "/OE1") (class "Default")
      (node (ref "U2") (pin "30") (pinfunction "~{OE}_30") (pintype "input"))
      (node (ref "U28") (pin "16") (pinfunction "IO13_16") (pintype "bidirectional"))
    )
    (net (code "75") (name "/OPRLED") (class "Default")
      (node (ref "R7") (pin "1") (pinfunction "1_1") (pintype "passive"))
      (node (ref "U28") (pin "37") (pinfunction "IO23_37") (pintype "bidirectional"))
    )
    (net (code "76") (name "/PWRLED") (class "Default")
      (node (ref "R6") (pin "1") (pinfunction "1_1") (pintype "passive"))
      (node (ref "U28") (pin "11") (pinfunction "I026_11") (pintype "bidirectional"))
    )
    (net (code "77") (name "/RST") (class "Default")
      (node (ref "C25") (pin "1") (pinfunction "1_1") (pintype "passive"))
      (node (ref "R15") (pin "1") (pinfunction "1_1") (pintype "passive"))
      (node (ref "RESET") (pin "2") (pinfunction "2_2") (pintype "bidirectional"))
      (node (ref "U11") (pin "3") (pinfunction "COLLECTOR_3") (pintype "output"))
      (node (ref "U28") (pin "3") (pinfunction "EN_3") (pintype "input"))
    )
    (net (code "78") (name "/RTS") (class "Default")
      (node (ref "R9") (pin "1") (pinfunction "1_1") (pintype "passive"))
      (node (ref "U11") (pin "2") (pinfunction "EMITTER_2") (pintype "passive"))
      (node (ref "U9") (pin "24") (pinfunction "RTS_24") (pintype "output"))
    )
    (net (code "79") (name "/RXD") (class "Default")
      (node (ref "U28") (pin "34") (pinfunction "RXD0_34") (pintype "bidirectional"))
      (node (ref "U9") (pin "26") (pinfunction "TXD_26") (pintype "output"))
    )
    (net (code "80") (name "/RXD_LED") (class "Default")
      (node (ref "D11") (pin "2") (pinfunction "2_2") (pintype "passive"))
      (node (ref "U9") (pin "18") (pinfunction "GPIO.1/RXT_18") (pintype "bidirectional"))
    )
    (net (code "81") (name "/SCL") (class "Default")
      (node (ref "R3") (pin "1") (pinfunction "1_1") (pintype "passive"))
      (node (ref "U$1") (pin "1") (pinfunction "SCL_1") (pintype "bidirectional"))
      (node (ref "U1") (pin "2") (pinfunction "SCL_2") (pintype "input"))
      (node (ref "U10") (pin "6") (pinfunction "SCL_6") (pintype "input"))
      (node (ref "U2") (pin "2") (pinfunction "SCL_2") (pintype "input"))
      (node (ref "U28") (pin "30") (pinfunction "IO18_30") (pintype "bidirectional"))
    )
    (net (code "82") (name "/SDA") (class "Default")
      (node (ref "R2") (pin "1") (pinfunction "1_1") (pintype "passive"))
      (node (ref "U$1") (pin "4") (pinfunction "SDA/CE_4") (pintype "bidirectional"))
      (node (ref "U1") (pin "1") (pinfunction "SDA_1") (pintype "bidirectional"))
      (node (ref "U10") (pin "1") (pinfunction "SDA_1") (pintype "bidirectional"))
      (node (ref "U2") (pin "1") (pinfunction "SDA_1") (pintype "bidirectional"))
      (node (ref "U28") (pin "31") (pinfunction "IO19_31") (pintype "bidirectional"))
    )
    (net (code "83") (name "/TXD") (class "Default")
      (node (ref "U28") (pin "35") (pinfunction "TXD0_35") (pintype "bidirectional"))
      (node (ref "U9") (pin "25") (pinfunction "RXD_25") (pintype "input"))
    )
    (net (code "84") (name "/TXD_LED") (class "Default")
      (node (ref "D10") (pin "2") (pinfunction "2_2") (pintype "passive"))
      (node (ref "U9") (pin "19") (pinfunction "GPIO.0/TXT_19") (pintype "bidirectional"))
    )
    (net (code "85") (name "/VBUS") (class "Default")
      (node (ref "C33") (pin "1") (pinfunction "1_1") (pintype "passive"))
      (node (ref "J1") (pin "A4B9") (pinfunction "VBUS_A4B9") (pintype "power_in"))
      (node (ref "J1") (pin "B4A9") (pinfunction "VBUS_B4A9") (pintype "power_in"))
      (node (ref "R21") (pin "2") (pinfunction "2_2") (pintype "passive"))
      (node (ref "U12") (pin "1") (pinfunction "D1+_1") (pintype "bidirectional"))
      (node (ref "U12") (pin "10") (pinfunction "NC_10") (pintype "passive"))
      (node (ref "U3") (pin "1") (pinfunction "IN_1") (pintype "input"))
      (node (ref "U3") (pin "3") (pinfunction "EN_3") (pintype "input"))
    )
    (net (code "86") (name "170V") (class "Default")
      (node (ref "20K") (pin "2") (pinfunction "2_2") (pintype "passive"))
      (node (ref "20K1") (pin "2") (pinfunction "2_2") (pintype "passive"))
      (node (ref "20K2") (pin "2") (pinfunction "2_2") (pintype "passive"))
      (node (ref "20K3") (pin "2") (pinfunction "2_2") (pintype "passive"))
      (node (ref "20K4") (pin "2") (pinfunction "2_2") (pintype "passive"))
      (node (ref "20K5") (pin "2") (pinfunction "2_2") (pintype "passive"))
      (node (ref "40K") (pin "1") (pinfunction "1_1") (pintype "passive"))
      (node (ref "C3") (pin "+") (pinfunction "+_+") (pintype "passive"))
      (node (ref "C4") (pin "+") (pinfunction "+_+") (pintype "passive"))
      (node (ref "C7") (pin "1") (pinfunction "1_1") (pintype "passive"))
      (node (ref "D12") (pin "12") (pinfunction "K_4_12") (pintype "bidirectional"))
      (node (ref "D12") (pin "7") (pinfunction "K_3_7") (pintype "bidirectional"))
      (node (ref "D12") (pin "8") (pinfunction "K_4_8") (pintype "bidirectional"))
      (node (ref "D12") (pin "9") (pinfunction "K_4_9") (pintype "bidirectional"))
      (node (ref "R24") (pin "2") (pinfunction "2_2") (pintype "passive"))
    )
    (net (code "87") (name "GND") (class "Default")
      (node (ref "0") (pin "1") (pinfunction "1_1") (pintype "passive"))
      (node (ref "0.05") (pin "1") (pinfunction "1_1") (pintype "passive"))
      (node (ref "C1") (pin "-") (pinfunction "-_-") (pintype "passive"))
      (node (ref "C11") (pin "2") (pinfunction "2_2") (pintype "passive"))
      (node (ref "C12") (pin "2") (pinfunction "2_2") (pintype "passive"))
      (node (ref "C13") (pin "2") (pinfunction "2_2") (pintype "passive"))
      (node (ref "C15") (pin "2") (pinfunction "2_2") (pintype "passive"))
      (node (ref "C17") (pin "1") (pinfunction "1_1") (pintype "passive"))
      (node (ref "C18") (pin "1") (pinfunction "1_1") (pintype "passive"))
      (node (ref "C2") (pin "-") (pinfunction "-_-") (pintype "passive"))
      (node (ref "C20") (pin "1") (pinfunction "1_1") (pintype "passive"))
      (node (ref "C25") (pin "2") (pinfunction "2_2") (pintype "passive"))
      (node (ref "C3") (pin "-") (pinfunction "-_-") (pintype "passive"))
      (node (ref "C30") (pin "2") (pinfunction "2_2") (pintype "passive"))
      (node (ref "C31") (pin "2") (pinfunction "2_2") (pintype "passive"))
      (node (ref "C32") (pin "2") (pinfunction "2_2") (pintype "passive"))
      (node (ref "C33") (pin "2") (pinfunction "2_2") (pintype "passive"))
      (node (ref "C34") (pin "2") (pinfunction "2_2") (pintype "passive"))
      (node (ref "C35") (pin "2") (pinfunction "2_2") (pintype "passive"))
      (node (ref "C36") (pin "2") (pinfunction "2_2") (pintype "passive"))
      (node (ref "C37") (pin "2") (pinfunction "2_2") (pintype "passive"))
      (node (ref "C39") (pin "2") (pinfunction "2_2") (pintype "passive"))
      (node (ref "C4") (pin "-") (pinfunction "-_-") (pintype "passive"))
      (node (ref "C5") (pin "2") (pinfunction "2_2") (pintype "passive"))
      (node (ref "C6") (pin "-") (pinfunction "-_-") (pintype "passive"))
      (node (ref "C8") (pin "2") (pinfunction "2_2") (pintype "passive"))
      (node (ref "D1") (pin "A") (pinfunction "C_A") (pintype "passive"))
      (node (ref "D12") (pin "10") (pinfunction "K_2_10") (pintype "bidirectional"))
      (node (ref "D12") (pin "11") (pinfunction "K_2_11") (pintype "bidirectional"))
      (node (ref "D12") (pin "3") (pinfunction "A_3_3") (pintype "bidirectional"))
      (node (ref "D12") (pin "4") (pinfunction "A_4_4") (pintype "bidirectional"))
      (node (ref "D12") (pin "5") (pinfunction "K_1_5") (pintype "bidirectional"))
      (node (ref "D12") (pin "6") (pinfunction "K_2_6") (pintype "bidirectional"))
      (node (ref "D2") (pin "2") (pinfunction "2_2") (pintype "passive"))
      (node (ref "D3") (pin "2") (pinfunction "2_2") (pintype "passive"))
      (node (ref "D4") (pin "2") (pinfunction "2_2") (pintype "passive"))
      (node (ref "D5") (pin "2") (pinfunction "2_2") (pintype "passive"))
      (node (ref "D6") (pin "2") (pinfunction "2_2") (pintype "passive"))
      (node (ref "D7") (pin "2") (pinfunction "2_2") (pintype "passive"))
      (node (ref "J1") (pin "A1B12") (pinfunction "GND_A1B12") (pintype "power_in"))
      (node (ref "J1") (pin "B1A12") (pinfunction "GND_B1A12") (pintype "power_in"))
      (node (ref "J1") (pin "S1") (pinfunction "SHIELD_S1") (pintype "passive"))
      (node (ref "J1") (pin "S2") (pinfunction "SHIELD_S2") (pintype "passive"))
      (node (ref "J1") (pin "S3") (pinfunction "SHIELD_S3") (pintype "passive"))
      (node (ref "J1") (pin "S4") (pinfunction "SHIELD_S4") (pintype "passive"))
      (node (ref "J2") (pin "GND") (pinfunction "GND_GND") (pintype "bidirectional"))
      (node (ref "R16") (pin "2") (pinfunction "2_2") (pintype "passive"))
      (node (ref "R17") (pin "1") (pinfunction "1_1") (pintype "passive"))
      (node (ref "R19") (pin "1") (pinfunction "1_1") (pintype "passive"))
      (node (ref "R32") (pin "2") (pinfunction "2_2") (pintype "passive"))
      (node (ref "RESET") (pin "1") (pinfunction "1_1") (pintype "bidirectional"))
      (node (ref "S1") (pin "MH1") (pinfunction "MH1_MH1") (pintype "bidirectional"))
      (node (ref "S1") (pin "MH2") (pinfunction "MH2_MH2") (pintype "bidirectional"))
      (node (ref "U$1") (pin "2") (pinfunction "SDI_2") (pintype "input"))
      (node (ref "U$1") (pin "8") (pinfunction "VSS_8") (pintype "bidirectional"))
      (node (ref "U1") (pin "11") (pinfunction "VSS_11") (pintype "power_in"))
      (node (ref "U1") (pin "23") (pinfunction "VSS_23") (pintype "power_in"))
      (node (ref "U1") (pin "27") (pinfunction "AD0_27") (pintype "input"))
      (node (ref "U1") (pin "28") (pinfunction "AD1_28") (pintype "input"))
      (node (ref "U1") (pin "29") (pinfunction "AD2_29") (pintype "input"))
      (node (ref "U1") (pin "34") (pinfunction "VSS_34") (pintype "power_in"))
      (node (ref "U1") (pin "39") (pinfunction "VSS_39") (pintype "power_in"))
      (node (ref "U1") (pin "51") (pinfunction "VSS_51") (pintype "power_in"))
      (node (ref "U1") (pin "6") (pinfunction "VSS_6") (pintype "power_in"))
      (node (ref "U10") (pin "2") (pinfunction "GND_2") (pintype "power_in"))
      (node (ref "U10") (pin "7") (pinfunction "EPAD_7") (pintype "passive"))
      (node (ref "U12") (pin "3") (pinfunction "GND_2_3") (pintype "power_in"))
      (node (ref "U12") (pin "8") (pinfunction "GND_8") (pintype "power_in"))
      (node (ref "U13") (pin "9") (pinfunction "GND_9") (pintype "power_in"))
      (node (ref "U14") (pin "9") (pinfunction "GND_9") (pintype "power_in"))
      (node (ref "U16") (pin "9") (pinfunction "GND_9") (pintype "power_in"))
      (node (ref "U17") (pin "9") (pinfunction "GND_9") (pintype "power_in"))
      (node (ref "U18") (pin "9") (pinfunction "GND_9") (pintype "power_in"))
      (node (ref "U19") (pin "9") (pinfunction "GND_9") (pintype "power_in"))
      (node (ref "U2") (pin "11") (pinfunction "VSS_11") (pintype "power_in"))
      (node (ref "U2") (pin "23") (pinfunction "VSS_23") (pintype "power_in"))
      (node (ref "U2") (pin "28") (pinfunction "AD1_28") (pintype "input"))
      (node (ref "U2") (pin "29") (pinfunction "AD2_29") (pintype "input"))
      (node (ref "U2") (pin "34") (pinfunction "VSS_34") (pintype "power_in"))
      (node (ref "U2") (pin "39") (pinfunction "VSS_39") (pintype "power_in"))
      (node (ref "U2") (pin "51") (pinfunction "VSS_51") (pintype "power_in"))
      (node (ref "U2") (pin "6") (pinfunction "VSS_6") (pintype "power_in"))
      (node (ref "U20") (pin "6") (pinfunction "AGND_6") (pintype "power_in"))
      (node (ref "U20") (pin "7") (pinfunction "GND_7") (pintype "power_in"))
      (node (ref "U25") (pin "10") (pinfunction "NC_3_10") (pintype "passive"))
      (node (ref "U25") (pin "11") (pinfunction "NC_11") (pintype "passive"))
      (node (ref "U25") (pin "12") (pinfunction "AGND_12") (pintype "passive"))
      (node (ref "U25") (pin "15") (pinfunction "PGND_15") (pintype "passive"))
      (node (ref "U25") (pin "3") (pinfunction "NC_2_3") (pintype "passive"))
      (node (ref "U26") (pin "2") (pinfunction "GND_2") (pintype "power_in"))
      (node (ref "U27") (pin "2") (pinfunction "GND_2") (pintype "power_in"))
      (node (ref "U28") (pin "1") (pinfunction "GND_1") (pintype "power_in"))
      (node (ref "U28") (pin "15") (pinfunction "GND_15") (pintype "power_in"))
      (node (ref "U28") (pin "38") (pinfunction "GND_38") (pintype "power_in"))
      (node (ref "U28") (pin "G.1") (pinfunction "GND_G.1") (pintype "power_in"))
      (node (ref "U28") (pin "G.10") (pinfunction "GND_G.10") (pintype "power_in"))
      (node (ref "U28") (pin "G.11") (pinfunction "GND_G.11") (pintype "power_in"))
      (node (ref "U28") (pin "G.12") (pinfunction "GND_G.12") (pintype "power_in"))
      (node (ref "U28") (pin "G.13") (pinfunction "GND_G.13") (pintype "power_in"))
      (node (ref "U28") (pin "G.14") (pinfunction "GND_G.14") (pintype "power_in"))
      (node (ref "U28") (pin "G.15") (pinfunction "GND_G.15") (pintype "power_in"))
      (node (ref "U28") (pin "G.16") (pinfunction "GND_G.16") (pintype "power_in"))
      (node (ref "U28") (pin "G.17") (pinfunction "GND_G.17") (pintype "power_in"))
      (node (ref "U28") (pin "G.18") (pinfunction "GND_G.18") (pintype "power_in"))
      (node (ref "U28") (pin "G.19") (pinfunction "GND_G.19") (pintype "power_in"))
      (node (ref "U28") (pin "G.2") (pinfunction "GND_G.2") (pintype "power_in"))
      (node (ref "U28") (pin "G.20") (pinfunction "GND_G.20") (pintype "power_in"))
      (node (ref "U28") (pin "G.21") (pinfunction "GND_G.21") (pintype "power_in"))
      (node (ref "U28") (pin "G.22") (pinfunction "GND_G.22") (pintype "power_in"))
      (node (ref "U28") (pin "G.4") (pinfunction "GND_G.4") (pintype "power_in"))
      (node (ref "U28") (pin "G.5") (pinfunction "GND_G.5") (pintype "power_in"))
      (node (ref "U28") (pin "G.6") (pinfunction "GND_G.6") (pintype "power_in"))
      (node (ref "U28") (pin "G.7") (pinfunction "GND_G.7") (pintype "power_in"))
      (node (ref "U28") (pin "G.8") (pinfunction "GND_G.8") (pintype "power_in"))
      (node (ref "U28") (pin "G.9") (pinfunction "GND_G.9") (pintype "power_in"))
      (node (ref "U29") (pin "2") (pinfunction "GND_2") (pintype "power_in"))
      (node (ref "U3") (pin "2") (pinfunction "GND_2") (pintype "input"))
      (node (ref "U30") (pin "2") (pinfunction "GND_2") (pintype "power_in"))
      (node (ref "U31") (pin "2") (pinfunction "GND_2") (pintype "power_in"))
      (node (ref "U32") (pin "2") (pinfunction "GND_2") (pintype "power_in"))
      (node (ref "U4") (pin "9") (pinfunction "GND_9") (pintype "power_in"))
      (node (ref "U5") (pin "3") (pinfunction "GND_3") (pintype "power_in"))
      (node (ref "U6") (pin "9") (pinfunction "GND_9") (pintype "power_in"))
      (node (ref "U9") (pin "29") (pinfunction "GND_29") (pintype "passive"))
      (node (ref "U9") (pin "3") (pinfunction "GND_2_3") (pintype "passive"))
    )
    (net (code "88") (name "Net-(20K-Pad1)") (class "Default")
      (node (ref "20K") (pin "1") (pinfunction "1_1") (pintype "passive"))
      (node (ref "N3") (pin "A") (pinfunction "A_A") (pintype "bidirectional"))
    )
    (net (code "89") (name "Net-(20K1-Pad1)") (class "Default")
      (node (ref "20K1") (pin "1") (pinfunction "1_1") (pintype "passive"))
      (node (ref "N1") (pin "A") (pinfunction "A_A") (pintype "bidirectional"))
    )
    (net (code "90") (name "Net-(20K2-Pad1)") (class "Default")
      (node (ref "20K2") (pin "1") (pinfunction "1_1") (pintype "passive"))
      (node (ref "N2") (pin "A") (pinfunction "A_A") (pintype "bidirectional"))
    )
    (net (code "91") (name "Net-(20K3-Pad1)") (class "Default")
      (node (ref "20K3") (pin "1") (pinfunction "1_1") (pintype "passive"))
      (node (ref "N6") (pin "A") (pinfunction "A_A") (pintype "bidirectional"))
    )
    (net (code "92") (name "Net-(20K4-Pad1)") (class "Default")
      (node (ref "20K4") (pin "1") (pinfunction "1_1") (pintype "passive"))
      (node (ref "N4") (pin "A") (pinfunction "A_A") (pintype "bidirectional"))
    )
    (net (code "93") (name "Net-(20K5-Pad1)") (class "Default")
      (node (ref "20K5") (pin "1") (pinfunction "1_1") (pintype "passive"))
      (node (ref "N5") (pin "A") (pinfunction "A_A") (pintype "bidirectional"))
    )
    (net (code "94") (name "Net-(D1-A)") (class "Default")
      (node (ref "40K") (pin "2") (pinfunction "2_2") (pintype "passive"))
      (node (ref "D1") (pin "C") (pinfunction "A_C") (pintype "passive"))
      (node (ref "U13") (pin "10") (pinfunction "COM_10") (pintype "bidirectional"))
      (node (ref "U14") (pin "10") (pinfunction "COM_10") (pintype "bidirectional"))
      (node (ref "U16") (pin "10") (pinfunction "COM_10") (pintype "bidirectional"))
      (node (ref "U17") (pin "10") (pinfunction "COM_10") (pintype "bidirectional"))
      (node (ref "U18") (pin "10") (pinfunction "COM_10") (pintype "bidirectional"))
      (node (ref "U19") (pin "10") (pinfunction "COM_10") (pintype "bidirectional"))
      (node (ref "U4") (pin "10") (pinfunction "COM_10") (pintype "bidirectional"))
      (node (ref "U6") (pin "10") (pinfunction "COM_10") (pintype "bidirectional"))
    )
    (net (code "95") (name "Net-(D2-Pad1)") (class "Default")
      (node (ref "D2") (pin "1") (pinfunction "1_1") (pintype "passive"))
      (node (ref "R6") (pin "2") (pinfunction "2_2") (pintype "passive"))
    )
    (net (code "96") (name "Net-(D3-Pad1)") (class "Default")
      (node (ref "D3") (pin "1") (pinfunction "1_1") (pintype "passive"))
      (node (ref "R5") (pin "2") (pinfunction "2_2") (pintype "passive"))
    )
    (net (code "97") (name "Net-(D4-Pad1)") (class "Default")
      (node (ref "D4") (pin "1") (pinfunction "1_1") (pintype "passive"))
      (node (ref "R10") (pin "2") (pinfunction "2_2") (pintype "passive"))
    )
    (net (code "98") (name "Net-(D5-Pad1)") (class "Default")
      (node (ref "D5") (pin "1") (pinfunction "1_1") (pintype "passive"))
      (node (ref "R31") (pin "2") (pinfunction "2_2") (pintype "passive"))
    )
    (net (code "99") (name "Net-(D6-Pad1)") (class "Default")
      (node (ref "D6") (pin "1") (pinfunction "1_1") (pintype "passive"))
      (node (ref "R13") (pin "2") (pinfunction "2_2") (pintype "passive"))
    )
    (net (code "100") (name "Net-(D7-Pad1)") (class "Default")
      (node (ref "D7") (pin "1") (pinfunction "1_1") (pintype "passive"))
      (node (ref "R7") (pin "2") (pinfunction "2_2") (pintype "passive"))
    )
    (net (code "101") (name "Net-(D10-Pad1)") (class "Default")
      (node (ref "D10") (pin "1") (pinfunction "1_1") (pintype "passive"))
      (node (ref "R11") (pin "2") (pinfunction "2_2") (pintype "passive"))
    )
    (net (code "102") (name "Net-(D11-Pad1)") (class "Default")
      (node (ref "D11") (pin "1") (pinfunction "1_1") (pintype "passive"))
      (node (ref "R23") (pin "2") (pinfunction "2_2") (pintype "passive"))
    )
    (net (code "103") (name "Net-(D12-A_1)") (class "Default")
      (node (ref "D12") (pin "1") (pinfunction "A_1_1") (pintype "bidirectional"))
      (node (ref "D12") (pin "2") (pinfunction "A_2_2") (pintype "bidirectional"))
      (node (ref "L1") (pin "2") (pinfunction "2_2") (pintype "passive"))
      (node (ref "Q1") (pin "5") (pinfunction "DRAIN_5") (pintype "passive"))
    )
    (net (code "104") (name "Net-(F1-Pad1)") (class "Default")
      (node (ref "F1") (pin "1") (pinfunction "1_1") (pintype "passive"))
      (node (ref "J2") (pin "PWR") (pinfunction "PWR_PWR") (pintype "bidirectional"))
    )
    (net (code "105") (name "Net-(F1-Pad2)") (class "Default")
      (node (ref "F1") (pin "2") (pinfunction "2_2") (pintype "passive"))
      (node (ref "S1") (pin "3") (pinfunction "3_3") (pintype "bidirectional"))
    )
    (net (code "106") (name "Net-(Q1-GATE)") (class "Default")
      (node (ref "Q1") (pin "1") (pinfunction "GATE_1") (pintype "passive"))
      (node (ref "U20") (pin "1") (pinfunction "EXT_1") (pintype "output"))
    )
    (net (code "107") (name "Net-(U$1-BBS)") (class "Default")
      (node (ref "U$1") (pin "18") (pinfunction "BBS_18") (pintype "bidirectional"))
      (node (ref "U$1") (pin "5") (pinfunction "IFS_5") (pintype "input"))
    )
    (net (code "108") (name "Net-(U$1-V_BAT)") (class "Default")
      (node (ref "R32") (pin "1") (pinfunction "1_1") (pintype "passive"))
      (node (ref "U$1") (pin "19") (pinfunction "V_BAT_19") (pintype "bidirectional"))
      (node (ref "U$2") (pin "P$1") (pinfunction "+_P$1") (pintype "bidirectional"))
      (node (ref "U$2") (pin "P$2") (pinfunction "+_P$2") (pintype "bidirectional"))
    )
    (net (code "109") (name "Net-(U1-~{INT{slash}SMBALERT})") (class "Default")
      (node (ref "R12") (pin "2") (pinfunction "2_2") (pintype "passive"))
      (node (ref "U1") (pin "55") (pinfunction "~{INT/SMBALERT}_55") (pintype "output"))
    )
    (net (code "110") (name "Net-(U1-~{RESET})") (class "Default")
      (node (ref "R1") (pin "1") (pinfunction "1_1") (pintype "passive"))
      (node (ref "U1") (pin "56") (pinfunction "~{RESET}_56") (pintype "input"))
    )
    (net (code "111") (name "Net-(U2-~{INT{slash}SMBALERT})") (class "Default")
      (node (ref "R4") (pin "2") (pinfunction "2_2") (pintype "passive"))
      (node (ref "U2") (pin "55") (pinfunction "~{INT/SMBALERT}_55") (pintype "output"))
    )
    (net (code "112") (name "Net-(U2-~{RESET})") (class "Default")
      (node (ref "R8") (pin "1") (pinfunction "1_1") (pintype "passive"))
      (node (ref "U2") (pin "56") (pinfunction "~{RESET}_56") (pintype "input"))
    )
    (net (code "113") (name "Net-(U4-1C)") (class "Default")
      (node (ref "N6") (pin "9") (pinfunction "9_9") (pintype "bidirectional"))
      (node (ref "U4") (pin "18") (pinfunction "1C_18") (pintype "output"))
    )
    (net (code "114") (name "Net-(U4-2C)") (class "Default")
      (node (ref "N6") (pin "8") (pinfunction "8_8") (pintype "bidirectional"))
      (node (ref "U4") (pin "17") (pinfunction "2C_17") (pintype "output"))
    )
    (net (code "115") (name "Net-(U4-3C)") (class "Default")
      (node (ref "N6") (pin "7") (pinfunction "7_7") (pintype "bidirectional"))
      (node (ref "U4") (pin "16") (pinfunction "3C_16") (pintype "output"))
    )
    (net (code "116") (name "Net-(U4-4C)") (class "Default")
      (node (ref "N6") (pin "6") (pinfunction "6_6") (pintype "bidirectional"))
      (node (ref "U4") (pin "15") (pinfunction "4C_15") (pintype "output"))
    )
    (net (code "117") (name "Net-(U4-5C)") (class "Default")
      (node (ref "N5") (pin "5") (pinfunction "5_5") (pintype "bidirectional"))
      (node (ref "U4") (pin "14") (pinfunction "5C_14") (pintype "output"))
    )
    (net (code "118") (name "Net-(U4-6C)") (class "Default")
      (node (ref "N5") (pin "4") (pinfunction "4_4") (pintype "bidirectional"))
      (node (ref "U4") (pin "13") (pinfunction "6C_13") (pintype "output"))
    )
    (net (code "119") (name "Net-(U4-7C)") (class "Default")
      (node (ref "N5") (pin "3") (pinfunction "3_3") (pintype "bidirectional"))
      (node (ref "U4") (pin "12") (pinfunction "7C_12") (pintype "output"))
    )
    (net (code "120") (name "Net-(U4-8C)") (class "Default")
      (node (ref "N5") (pin "2") (pinfunction "2_2") (pintype "bidirectional"))
      (node (ref "U4") (pin "11") (pinfunction "8C_11") (pintype "output"))
    )
    (net (code "121") (name "Net-(U5-LX)") (class "Default")
      (node (ref "L4") (pin "2") (pinfunction "2_2") (pintype "passive"))
      (node (ref "U5") (pin "2") (pinfunction "LX_2") (pintype "output"))
    )
    (net (code "122") (name "Net-(U5-SEL)") (class "Default")
      (node (ref "0") (pin "2") (pinfunction "2_2") (pintype "passive"))
      (node (ref "U5") (pin "4") (pinfunction "SEL_4") (pintype "input"))
    )
    (net (code "123") (name "Net-(U6-3C)") (class "Default")
      (node (ref "N6") (pin "5") (pinfunction "5_5") (pintype "bidirectional"))
      (node (ref "U6") (pin "16") (pinfunction "3C_16") (pintype "output"))
    )
    (net (code "124") (name "Net-(U6-4C)") (class "Default")
      (node (ref "N6") (pin "4") (pinfunction "4_4") (pintype "bidirectional"))
      (node (ref "U6") (pin "15") (pinfunction "4C_15") (pintype "output"))
    )
    (net (code "125") (name "Net-(U6-5C)") (class "Default")
      (node (ref "N6") (pin "3") (pinfunction "3_3") (pintype "bidirectional"))
      (node (ref "U6") (pin "14") (pinfunction "5C_14") (pintype "output"))
    )
    (net (code "126") (name "Net-(U6-6C)") (class "Default")
      (node (ref "N6") (pin "2") (pinfunction "2_2") (pintype "bidirectional"))
      (node (ref "U6") (pin "13") (pinfunction "6C_13") (pintype "output"))
    )
    (net (code "127") (name "Net-(U6-7C)") (class "Default")
      (node (ref "N6") (pin "1") (pinfunction "1_1") (pintype "bidirectional"))
      (node (ref "U6") (pin "12") (pinfunction "7C_12") (pintype "output"))
    )
    (net (code "128") (name "Net-(U6-8C)") (class "Default")
      (node (ref "N6") (pin "0") (pinfunction "0_0") (pintype "bidirectional"))
      (node (ref "U6") (pin "11") (pinfunction "8C_11") (pintype "output"))
    )
    (net (code "129") (name "Net-(U7-BASE)") (class "Default")
      (node (ref "R9") (pin "2") (pinfunction "2_2") (pintype "passive"))
      (node (ref "U7") (pin "1") (pinfunction "BASE_1") (pintype "input"))
    )
    (net (code "130") (name "Net-(U9A-RSTB)") (class "Default")
      (node (ref "R22") (pin "2") (pinfunction "2_2") (pintype "passive"))
      (node (ref "U9") (pin "9") (pinfunction "RSTB_9") (pintype "passive"))
    )
    (net (code "131") (name "Net-(U9A-VBUS)") (class "Default")
      (node (ref "R17") (pin "2") (pinfunction "2_2") (pintype "passive"))
      (node (ref "R21") (pin "1") (pinfunction "1_1") (pintype "passive"))
      (node (ref "U9") (pin "8") (pinfunction "VBUS_8") (pintype "input"))
    )
    (net (code "132") (name "Net-(U11-BASE)") (class "Default")
      (node (ref "R20") (pin "2") (pinfunction "2_2") (pintype "passive"))
      (node (ref "U11") (pin "1") (pinfunction "BASE_1") (pintype "input"))
    )
    (net (code "133") (name "Net-(U13-1C)") (class "Default")
      (node (ref "N3") (pin "9") (pinfunction "9_9") (pintype "bidirectional"))
      (node (ref "U13") (pin "18") (pinfunction "1C_18") (pintype "output"))
    )
    (net (code "134") (name "Net-(U13-2C)") (class "Default")
      (node (ref "N3") (pin "8") (pinfunction "8_8") (pintype "bidirectional"))
      (node (ref "U13") (pin "17") (pinfunction "2C_17") (pintype "output"))
    )
    (net (code "135") (name "Net-(U13-3C)") (class "Default")
      (node (ref "N3") (pin "7") (pinfunction "7_7") (pintype "bidirectional"))
      (node (ref "U13") (pin "16") (pinfunction "3C_16") (pintype "output"))
    )
    (net (code "136") (name "Net-(U13-4C)") (class "Default")
      (node (ref "N3") (pin "6") (pinfunction "6_6") (pintype "bidirectional"))
      (node (ref "U13") (pin "15") (pinfunction "4C_15") (pintype "output"))
    )
    (net (code "137") (name "Net-(U13-5C)") (class "Default")
      (node (ref "N2") (pin "5") (pinfunction "5_5") (pintype "bidirectional"))
      (node (ref "U13") (pin "14") (pinfunction "5C_14") (pintype "output"))
    )
    (net (code "138") (name "Net-(U13-6C)") (class "Default")
      (node (ref "N2") (pin "4") (pinfunction "4_4") (pintype "bidirectional"))
      (node (ref "U13") (pin "13") (pinfunction "6C_13") (pintype "output"))
    )
    (net (code "139") (name "Net-(U13-7C)") (class "Default")
      (node (ref "N2") (pin "3") (pinfunction "3_3") (pintype "bidirectional"))
      (node (ref "U13") (pin "12") (pinfunction "7C_12") (pintype "output"))
    )
    (net (code "140") (name "Net-(U13-8C)") (class "Default")
      (node (ref "N2") (pin "2") (pinfunction "2_2") (pintype "bidirectional"))
      (node (ref "U13") (pin "11") (pinfunction "8C_11") (pintype "output"))
    )
    (net (code "141") (name "Net-(U14-3C)") (class "Default")
      (node (ref "N3") (pin "5") (pinfunction "5_5") (pintype "bidirectional"))
      (node (ref "U14") (pin "16") (pinfunction "3C_16") (pintype "output"))
    )
    (net (code "142") (name "Net-(U14-4C)") (class "Default")
      (node (ref "N3") (pin "4") (pinfunction "4_4") (pintype "bidirectional"))
      (node (ref "U14") (pin "15") (pinfunction "4C_15") (pintype "output"))
    )
    (net (code "143") (name "Net-(U14-5C)") (class "Default")
      (node (ref "N3") (pin "3") (pinfunction "3_3") (pintype "bidirectional"))
      (node (ref "U14") (pin "14") (pinfunction "5C_14") (pintype "output"))
    )
    (net (code "144") (name "Net-(U14-6C)") (class "Default")
      (node (ref "N3") (pin "2") (pinfunction "2_2") (pintype "bidirectional"))
      (node (ref "U14") (pin "13") (pinfunction "6C_13") (pintype "output"))
    )
    (net (code "145") (name "Net-(U14-7C)") (class "Default")
      (node (ref "N3") (pin "1") (pinfunction "1_1") (pintype "bidirectional"))
      (node (ref "U14") (pin "12") (pinfunction "7C_12") (pintype "output"))
    )
    (net (code "146") (name "Net-(U14-8C)") (class "Default")
      (node (ref "N3") (pin "0") (pinfunction "0_0") (pintype "bidirectional"))
      (node (ref "U14") (pin "11") (pinfunction "8C_11") (pintype "output"))
    )
    (net (code "147") (name "Net-(U16-1C)") (class "Default")
      (node (ref "N4") (pin "3") (pinfunction "3_3") (pintype "bidirectional"))
      (node (ref "U16") (pin "18") (pinfunction "1C_18") (pintype "output"))
    )
    (net (code "148") (name "Net-(U16-2C)") (class "Default")
      (node (ref "N4") (pin "2") (pinfunction "2_2") (pintype "bidirectional"))
      (node (ref "U16") (pin "17") (pinfunction "2C_17") (pintype "output"))
    )
    (net (code "149") (name "Net-(U16-3C)") (class "Default")
      (node (ref "N4") (pin "1") (pinfunction "1_1") (pintype "bidirectional"))
      (node (ref "U16") (pin "16") (pinfunction "3C_16") (pintype "output"))
    )
    (net (code "150") (name "Net-(U16-4C)") (class "Default")
      (node (ref "N4") (pin "0") (pinfunction "0_0") (pintype "bidirectional"))
      (node (ref "U16") (pin "15") (pinfunction "4C_15") (pintype "output"))
    )
    (net (code "151") (name "Net-(U16-5C)") (class "Default")
      (node (ref "N4") (pin "9") (pinfunction "9_9") (pintype "bidirectional"))
      (node (ref "U16") (pin "14") (pinfunction "5C_14") (pintype "output"))
    )
    (net (code "152") (name "Net-(U16-6C)") (class "Default")
      (node (ref "N4") (pin "8") (pinfunction "8_8") (pintype "bidirectional"))
      (node (ref "U16") (pin "13") (pinfunction "6C_13") (pintype "output"))
    )
    (net (code "153") (name "Net-(U16-7C)") (class "Default")
      (node (ref "N4") (pin "7") (pinfunction "7_7") (pintype "bidirectional"))
      (node (ref "U16") (pin "12") (pinfunction "7C_12") (pintype "output"))
    )
    (net (code "154") (name "Net-(U16-8C)") (class "Default")
      (node (ref "N4") (pin "6") (pinfunction "6_6") (pintype "bidirectional"))
      (node (ref "U16") (pin "11") (pinfunction "8C_11") (pintype "output"))
    )
    (net (code "155") (name "Net-(U17-1C)") (class "Default")
      (node (ref "N1") (pin "3") (pinfunction "3_3") (pintype "bidirectional"))
      (node (ref "U17") (pin "18") (pinfunction "1C_18") (pintype "output"))
    )
    (net (code "156") (name "Net-(U17-2C)") (class "Default")
      (node (ref "N1") (pin "2") (pinfunction "2_2") (pintype "bidirectional"))
      (node (ref "U17") (pin "17") (pinfunction "2C_17") (pintype "output"))
    )
    (net (code "157") (name "Net-(U17-3C)") (class "Default")
      (node (ref "N1") (pin "1") (pinfunction "1_1") (pintype "bidirectional"))
      (node (ref "U17") (pin "16") (pinfunction "3C_16") (pintype "output"))
    )
    (net (code "158") (name "Net-(U17-4C)") (class "Default")
      (node (ref "N1") (pin "0") (pinfunction "0_0") (pintype "bidirectional"))
      (node (ref "U17") (pin "15") (pinfunction "4C_15") (pintype "output"))
    )
    (net (code "159") (name "Net-(U17-5C)") (class "Default")
      (node (ref "N1") (pin "9") (pinfunction "9_9") (pintype "bidirectional"))
      (node (ref "U17") (pin "14") (pinfunction "5C_14") (pintype "output"))
    )
    (net (code "160") (name "Net-(U17-6C)") (class "Default")
      (node (ref "N1") (pin "8") (pinfunction "8_8") (pintype "bidirectional"))
      (node (ref "U17") (pin "13") (pinfunction "6C_13") (pintype "output"))
    )
    (net (code "161") (name "Net-(U17-7C)") (class "Default")
      (node (ref "N1") (pin "7") (pinfunction "7_7") (pintype "bidirectional"))
      (node (ref "U17") (pin "12") (pinfunction "7C_12") (pintype "output"))
    )
    (net (code "162") (name "Net-(U17-8C)") (class "Default")
      (node (ref "N1") (pin "6") (pinfunction "6_6") (pintype "bidirectional"))
      (node (ref "U17") (pin "11") (pinfunction "8C_11") (pintype "output"))
    )
    (net (code "163") (name "Net-(U18-1C)") (class "Default")
      (node (ref "N2") (pin "1") (pinfunction "1_1") (pintype "bidirectional"))
      (node (ref "U18") (pin "18") (pinfunction "1C_18") (pintype "output"))
    )
    (net (code "164") (name "Net-(U18-2C)") (class "Default")
      (node (ref "N2") (pin "0") (pinfunction "0_0") (pintype "bidirectional"))
      (node (ref "U18") (pin "17") (pinfunction "2C_17") (pintype "output"))
    )
    (net (code "165") (name "Net-(U18-3C)") (class "Default")
      (node (ref "N2") (pin "9") (pinfunction "9_9") (pintype "bidirectional"))
      (node (ref "U18") (pin "16") (pinfunction "3C_16") (pintype "output"))
    )
    (net (code "166") (name "Net-(U18-4C)") (class "Default")
      (node (ref "N2") (pin "8") (pinfunction "8_8") (pintype "bidirectional"))
      (node (ref "U18") (pin "15") (pinfunction "4C_15") (pintype "output"))
    )
    (net (code "167") (name "Net-(U18-5C)") (class "Default")
      (node (ref "N2") (pin "7") (pinfunction "7_7") (pintype "bidirectional"))
      (node (ref "U18") (pin "14") (pinfunction "5C_14") (pintype "output"))
    )
    (net (code "168") (name "Net-(U18-6C)") (class "Default")
      (node (ref "N2") (pin "6") (pinfunction "6_6") (pintype "bidirectional"))
      (node (ref "U18") (pin "13") (pinfunction "6C_13") (pintype "output"))
    )
    (net (code "169") (name "Net-(U18-7C)") (class "Default")
      (node (ref "N1") (pin "5") (pinfunction "5_5") (pintype "bidirectional"))
      (node (ref "U18") (pin "12") (pinfunction "7C_12") (pintype "output"))
    )
    (net (code "170") (name "Net-(U18-8C)") (class "Default")
      (node (ref "N1") (pin "4") (pinfunction "4_4") (pintype "bidirectional"))
      (node (ref "U18") (pin "11") (pinfunction "8C_11") (pintype "output"))
    )
    (net (code "171") (name "Net-(U19-1C)") (class "Default")
      (node (ref "N5") (pin "1") (pinfunction "1_1") (pintype "bidirectional"))
      (node (ref "U19") (pin "18") (pinfunction "1C_18") (pintype "output"))
    )
    (net (code "172") (name "Net-(U19-2C)") (class "Default")
      (node (ref "N5") (pin "0") (pinfunction "0_0") (pintype "bidirectional"))
      (node (ref "U19") (pin "17") (pinfunction "2C_17") (pintype "output"))
    )
    (net (code "173") (name "Net-(U19-3C)") (class "Default")
      (node (ref "N5") (pin "9") (pinfunction "9_9") (pintype "bidirectional"))
      (node (ref "U19") (pin "16") (pinfunction "3C_16") (pintype "output"))
    )
    (net (code "174") (name "Net-(U19-4C)") (class "Default")
      (node (ref "N5") (pin "8") (pinfunction "8_8") (pintype "bidirectional"))
      (node (ref "U19") (pin "15") (pinfunction "4C_15") (pintype "output"))
    )
    (net (code "175") (name "Net-(U19-5C)") (class "Default")
      (node (ref "N5") (pin "7") (pinfunction "7_7") (pintype "bidirectional"))
      (node (ref "U19") (pin "14") (pinfunction "5C_14") (pintype "output"))
    )
    (net (code "176") (name "Net-(U19-6C)") (class "Default")
      (node (ref "N5") (pin "6") (pinfunction "6_6") (pintype "bidirectional"))
      (node (ref "U19") (pin "13") (pinfunction "6C_13") (pintype "output"))
    )
    (net (code "177") (name "Net-(U19-7C)") (class "Default")
      (node (ref "N4") (pin "5") (pinfunction "5_5") (pintype "bidirectional"))
      (node (ref "U19") (pin "12") (pinfunction "7C_12") (pintype "output"))
    )
    (net (code "178") (name "Net-(U19-8C)") (class "Default")
      (node (ref "N4") (pin "4") (pinfunction "4_4") (pintype "bidirectional"))
      (node (ref "U19") (pin "11") (pinfunction "8C_11") (pintype "output"))
    )
    (net (code "179") (name "Net-(U20-CS)") (class "Default")
      (node (ref "0.05") (pin "2") (pinfunction "2_2") (pintype "passive"))
      (node (ref "Q1") (pin "2") (pinfunction "SOURCE_2") (pintype "passive"))
      (node (ref "Q1") (pin "3") (pinfunction "SOURCE_3") (pintype "passive"))
      (node (ref "Q1") (pin "4") (pinfunction "SOURCE_4") (pintype "passive"))
      (node (ref "U20") (pin "8") (pinfunction "CS_8") (pintype "input"))
    )
    (net (code "180") (name "Net-(U20-FB)") (class "Default")
      (node (ref "C7") (pin "2") (pinfunction "2_2") (pintype "passive"))
      (node (ref "R24") (pin "1") (pinfunction "1_1") (pintype "passive"))
      (node (ref "U20") (pin "3") (pinfunction "FB_3") (pintype "input"))
      (node (ref "VR1") (pin "3") (pinfunction "CW_3") (pintype "passive"))
    )
    (net (code "181") (name "Net-(U20-REF)") (class "Default")
      (node (ref "C5") (pin "1") (pinfunction "1_1") (pintype "passive"))
      (node (ref "U20") (pin "5") (pinfunction "REF_5") (pintype "output"))
    )
    (net (code "182") (name "Net-(U25-FB)") (class "Default")
      (node (ref "R14") (pin "1") (pinfunction "1_1") (pintype "passive"))
      (node (ref "R16") (pin "1") (pinfunction "1_1") (pintype "passive"))
      (node (ref "U25") (pin "9") (pinfunction "FB_9") (pintype "passive"))
    )
    (net (code "183") (name "Net-(U26-DO)") (class "Default")
      (node (ref "U26") (pin "1") (pinfunction "DO_1") (pintype "output"))
      (node (ref "U27") (pin "3") (pinfunction "DI_3") (pintype "input"))
    )
    (net (code "184") (name "Net-(U27-DO)") (class "Default")
      (node (ref "U27") (pin "1") (pinfunction "DO_1") (pintype "output"))
      (node (ref "U29") (pin "3") (pinfunction "DI_3") (pintype "input"))
    )
    (net (code "185") (name "Net-(U29-DO)") (class "Default")
      (node (ref "U29") (pin "1") (pinfunction "DO_1") (pintype "output"))
      (node (ref "U30") (pin "3") (pinfunction "DI_3") (pintype "input"))
    )
    (net (code "186") (name "Net-(U30-DO)") (class "Default")
      (node (ref "U30") (pin "1") (pinfunction "DO_1") (pintype "output"))
      (node (ref "U31") (pin "3") (pinfunction "DI_3") (pintype "input"))
    )
    (net (code "187") (name "Net-(U31-DO)") (class "Default")
      (node (ref "U31") (pin "1") (pinfunction "DO_1") (pintype "output"))
      (node (ref "U32") (pin "3") (pinfunction "DI_3") (pintype "input"))
    )
    (net (code "188") (name "Net-(VR1-CCW)") (class "Default")
      (node (ref "R19") (pin "2") (pinfunction "2_2") (pintype "passive"))
      (node (ref "VR1") (pin "1") (pinfunction "CCW_1") (pintype "passive"))
      (node (ref "VR1") (pin "2") (pinfunction "WIPER_2") (pintype "passive"))
    )
    (net (code "189") (name "VCC") (class "Default")
      (node (ref "C1") (pin "+") (pinfunction "+_+") (pintype "passive"))
      (node (ref "C12") (pin "1") (pinfunction "1_1") (pintype "passive"))
      (node (ref "C13") (pin "1") (pinfunction "1_1") (pintype "passive"))
      (node (ref "C2") (pin "+") (pinfunction "+_+") (pintype "passive"))
      (node (ref "C6") (pin "+") (pinfunction "+_+") (pintype "passive"))
      (node (ref "L1") (pin "1") (pinfunction "1_1") (pintype "passive"))
      (node (ref "S1") (pin "1") (pinfunction "1_1") (pintype "bidirectional"))
      (node (ref "S1") (pin "2") (pinfunction "2_2") (pintype "bidirectional"))
      (node (ref "U20") (pin "2") (pinfunction "V+_2") (pintype "input"))
      (node (ref "U25") (pin "1") (pinfunction "VIN_2_1") (pintype "passive"))
      (node (ref "U25") (pin "14") (pinfunction "VIN_14") (pintype "passive"))
      (node (ref "U25") (pin "2") (pinfunction "EN_2") (pintype "passive"))
    )
    (net (code "190") (name "VDD") (class "Default")
      (node (ref "C11") (pin "1") (pinfunction "1_1") (pintype "passive"))
      (node (ref "C15") (pin "1") (pinfunction "1_1") (pintype "passive"))
      (node (ref "C17") (pin "2") (pinfunction "2_2") (pintype "passive"))
      (node (ref "C18") (pin "2") (pinfunction "2_2") (pintype "passive"))
      (node (ref "C30") (pin "1") (pinfunction "1_1") (pintype "passive"))
      (node (ref "C31") (pin "1") (pinfunction "1_1") (pintype "passive"))
      (node (ref "C32") (pin "1") (pinfunction "1_1") (pintype "passive"))
      (node (ref "C34") (pin "1") (pinfunction "1_1") (pintype "passive"))
      (node (ref "C35") (pin "1") (pinfunction "1_1") (pintype "passive"))
      (node (ref "C36") (pin "1") (pinfunction "1_1") (pintype "passive"))
      (node (ref "C37") (pin "1") (pinfunction "1_1") (pintype "passive"))
      (node (ref "C39") (pin "1") (pinfunction "1_1") (pintype "passive"))
      (node (ref "C8") (pin "1") (pinfunction "1_1") (pintype "passive"))
      (node (ref "L4") (pin "1") (pinfunction "1_1") (pintype "passive"))
      (node (ref "R1") (pin "2") (pinfunction "2_2") (pintype "passive"))
      (node (ref "R10") (pin "1") (pinfunction "1_1") (pintype "passive"))
      (node (ref "R11") (pin "1") (pinfunction "1_1") (pintype "passive"))
      (node (ref "R12") (pin "1") (pinfunction "1_1") (pintype "passive"))
      (node (ref "R14") (pin "2") (pinfunction "2_2") (pintype "passive"))
      (node (ref "R15") (pin "2") (pinfunction "2_2") (pintype "passive"))
      (node (ref "R2") (pin "2") (pinfunction "2_2") (pintype "passive"))
      (node (ref "R22") (pin "1") (pinfunction "1_1") (pintype "passive"))
      (node (ref "R23") (pin "1") (pinfunction "1_1") (pintype "passive"))
      (node (ref "R3") (pin "2") (pinfunction "2_2") (pintype "passive"))
      (node (ref "R4") (pin "1") (pinfunction "1_1") (pintype "passive"))
      (node (ref "R8") (pin "2") (pinfunction "2_2") (pintype "passive"))
      (node (ref "U$1") (pin "20") (pinfunction "VDD_20") (pintype "bidirectional"))
      (node (ref "U1") (pin "18") (pinfunction "VDD_18") (pintype "power_in"))
      (node (ref "U1") (pin "46") (pinfunction "VDD_46") (pintype "power_in"))
      (node (ref "U10") (pin "5") (pinfunction "VDD_5") (pintype "power_in"))
      (node (ref "U2") (pin "18") (pinfunction "VDD_18") (pintype "power_in"))
      (node (ref "U2") (pin "27") (pinfunction "AD0_27") (pintype "input"))
      (node (ref "U2") (pin "46") (pinfunction "VDD_46") (pintype "power_in"))
      (node (ref "U25") (pin "7") (pinfunction "VOUT_2_7") (pintype "passive"))
      (node (ref "U25") (pin "8") (pinfunction "VOUT_8") (pintype "passive"))
      (node (ref "U28") (pin "2") (pinfunction "3V3_2") (pintype "power_in"))
      (node (ref "U3") (pin "5") (pinfunction "OUT_5") (pintype "passive"))
      (node (ref "U5") (pin "5") (pinfunction "IN_5") (pintype "input"))
      (node (ref "U9") (pin "6") (pinfunction "VDD_6") (pintype "power_in"))
      (node (ref "U9") (pin "7") (pinfunction "VREGIN_7") (pintype "power_in"))
    )
    (net (code "191") (name "unconnected-(J1-CC1-PadA5)") (class "Default")
      (node (ref "J1") (pin "A5") (pinfunction "CC1_A5") (pintype "bidirectional"))
    )
    (net (code "192") (name "unconnected-(J1-CC2-PadB5)") (class "Default")
      (node (ref "J1") (pin "B5") (pinfunction "CC2_B5") (pintype "bidirectional"))
    )
    (net (code "193") (name "unconnected-(J1-SBU1-PadA8)") (class "Default")
      (node (ref "J1") (pin "A8") (pinfunction "SBU1_A8") (pintype "bidirectional"))
    )
    (net (code "194") (name "unconnected-(J1-SBU2-PadB8)") (class "Default")
      (node (ref "J1") (pin "B8") (pinfunction "SBU2_B8") (pintype "bidirectional"))
    )
    (net (code "195") (name "unconnected-(J2-PadGNDBREAK)") (class "Default")
      (node (ref "J2") (pin "GNDBREAK") (pinfunction "GNDBREAK_GNDBREAK") (pintype "bidirectional"))
    )
    (net (code "196") (name "unconnected-(MGT1-PadP$1)") (class "Default")
      (node (ref "MGT1") (pin "P$1") (pinfunction "P$1_P$1") (pintype "bidirectional"))
    )
    (net (code "197") (name "unconnected-(MGT2-PadP$1)") (class "Default")
      (node (ref "MGT2") (pin "P$1") (pinfunction "P$1_P$1") (pintype "bidirectional"))
    )
    (net (code "198") (name "unconnected-(MGT3-PadP$1)") (class "Default")
      (node (ref "MGT3") (pin "P$1") (pinfunction "P$1_P$1") (pintype "bidirectional"))
    )
    (net (code "199") (name "unconnected-(MGT4-PadP$1)") (class "Default")
      (node (ref "MGT4") (pin "P$1") (pinfunction "P$1_P$1") (pintype "bidirectional"))
    )
    (net (code "200") (name "unconnected-(N1-PadLHDP)") (class "Default")
      (node (ref "N1") (pin "LHDP") (pinfunction "LHDP_LHDP") (pintype "bidirectional"))
    )
    (net (code "201") (name "unconnected-(N1-PadRHDP)") (class "Default")
      (node (ref "N1") (pin "RHDP") (pinfunction "RHDP_RHDP") (pintype "bidirectional"))
    )
    (net (code "202") (name "unconnected-(N2-PadLHDP)") (class "Default")
      (node (ref "N2") (pin "LHDP") (pinfunction "LHDP_LHDP") (pintype "bidirectional"))
    )
    (net (code "203") (name "unconnected-(N2-PadRHDP)") (class "Default")
      (node (ref "N2") (pin "RHDP") (pinfunction "RHDP_RHDP") (pintype "bidirectional"))
    )
    (net (code "204") (name "unconnected-(N3-PadLHDP)") (class "Default")
      (node (ref "N3") (pin "LHDP") (pinfunction "LHDP_LHDP") (pintype "bidirectional"))
    )
    (net (code "205") (name "unconnected-(N3-PadRHDP)") (class "Default")
      (node (ref "N3") (pin "RHDP") (pinfunction "RHDP_RHDP") (pintype "bidirectional"))
    )
    (net (code "206") (name "unconnected-(N4-PadLHDP)") (class "Default")
      (node (ref "N4") (pin "LHDP") (pinfunction "LHDP_LHDP") (pintype "bidirectional"))
    )
    (net (code "207") (name "unconnected-(N4-PadRHDP)") (class "Default")
      (node (ref "N4") (pin "RHDP") (pinfunction "RHDP_RHDP") (pintype "bidirectional"))
    )
    (net (code "208") (name "unconnected-(N5-PadLHDP)") (class "Default")
      (node (ref "N5") (pin "LHDP") (pinfunction "LHDP_LHDP") (pintype "bidirectional"))
    )
    (net (code "209") (name "unconnected-(N5-PadRHDP)") (class "Default")
      (node (ref "N5") (pin "RHDP") (pinfunction "RHDP_RHDP") (pintype "bidirectional"))
    )
    (net (code "210") (name "unconnected-(N6-PadLHDP)") (class "Default")
      (node (ref "N6") (pin "LHDP") (pinfunction "LHDP_LHDP") (pintype "bidirectional"))
    )
    (net (code "211") (name "unconnected-(N6-PadRHDP)") (class "Default")
      (node (ref "N6") (pin "RHDP") (pinfunction "RHDP_RHDP") (pintype "bidirectional"))
    )
    (net (code "212") (name "unconnected-(U$1-CLKOUT-Pad7)") (class "Default")
      (node (ref "U$1") (pin "7") (pinfunction "CLKOUT_7") (pintype "output"))
    )
    (net (code "213") (name "unconnected-(U$1-N.C.9-Pad9)") (class "Default")
      (node (ref "U$1") (pin "9") (pinfunction "N.C.9_9") (pintype "no_connect"))
    )
    (net (code "214") (name "unconnected-(U$1-N.C.10-Pad10)") (class "Default")
      (node (ref "U$1") (pin "10") (pinfunction "N.C.10_10") (pintype "no_connect"))
    )
    (net (code "215") (name "unconnected-(U$1-N.C.11-Pad11)") (class "Default")
      (node (ref "U$1") (pin "11") (pinfunction "N.C.11_11") (pintype "no_connect"))
    )
    (net (code "216") (name "unconnected-(U$1-N.C.12-Pad12)") (class "Default")
      (node (ref "U$1") (pin "12") (pinfunction "N.C.12_12") (pintype "no_connect"))
    )
    (net (code "217") (name "unconnected-(U$1-N.C.13-Pad13)") (class "Default")
      (node (ref "U$1") (pin "13") (pinfunction "N.C.13_13") (pintype "no_connect"))
    )
    (net (code "218") (name "unconnected-(U$1-N.C.14-Pad14)") (class "Default")
      (node (ref "U$1") (pin "14") (pinfunction "N.C.14_14") (pintype "no_connect"))
    )
    (net (code "219") (name "unconnected-(U$1-N.C.15-Pad15)") (class "Default")
      (node (ref "U$1") (pin "15") (pinfunction "N.C.15_15") (pintype "no_connect"))
    )
    (net (code "220") (name "unconnected-(U$1-N.C.16-Pad16)") (class "Default")
      (node (ref "U$1") (pin "16") (pinfunction "N.C.16_16") (pintype "no_connect"))
    )
    (net (code "221") (name "unconnected-(U$1-SDO-Pad3)") (class "Default")
      (node (ref "U$1") (pin "3") (pinfunction "SDO_3") (pintype "output"))
    )
    (net (code "222") (name "unconnected-(U1-IO2_0-Pad22)") (class "Default")
      (node (ref "U1") (pin "22") (pinfunction "IO2_0_22") (pintype "bidirectional"))
    )
    (net (code "223") (name "unconnected-(U1-IO2_1-Pad24)") (class "Default")
      (node (ref "U1") (pin "24") (pinfunction "IO2_1_24") (pintype "bidirectional"))
    )
    (net (code "224") (name "unconnected-(U1-IO2_2-Pad25)") (class "Default")
      (node (ref "U1") (pin "25") (pinfunction "IO2_2_25") (pintype "bidirectional"))
    )
    (net (code "225") (name "unconnected-(U1-IO2_3-Pad26)") (class "Default")
      (node (ref "U1") (pin "26") (pinfunction "IO2_3_26") (pintype "bidirectional"))
    )
    (net (code "226") (name "unconnected-(U1-IO2_4-Pad31)") (class "Default")
      (node (ref "U1") (pin "31") (pinfunction "IO2_4_31") (pintype "bidirectional"))
    )
    (net (code "227") (name "unconnected-(U1-IO2_5-Pad32)") (class "Default")
      (node (ref "U1") (pin "32") (pinfunction "IO2_5_32") (pintype "bidirectional"))
    )
    (net (code "228") (name "unconnected-(U1-IO2_6-Pad33)") (class "Default")
      (node (ref "U1") (pin "33") (pinfunction "IO2_6_33") (pintype "bidirectional"))
    )
    (net (code "229") (name "unconnected-(U1-IO2_7-Pad35)") (class "Default")
      (node (ref "U1") (pin "35") (pinfunction "IO2_7_35") (pintype "bidirectional"))
    )
    (net (code "230") (name "unconnected-(U1-IO4_0-Pad45)") (class "Default")
      (node (ref "U1") (pin "45") (pinfunction "IO4_0_45") (pintype "bidirectional"))
    )
    (net (code "231") (name "unconnected-(U1-IO4_1-Pad47)") (class "Default")
      (node (ref "U1") (pin "47") (pinfunction "IO4_1_47") (pintype "bidirectional"))
    )
    (net (code "232") (name "unconnected-(U2-IO2_0-Pad22)") (class "Default")
      (node (ref "U2") (pin "22") (pinfunction "IO2_0_22") (pintype "bidirectional"))
    )
    (net (code "233") (name "unconnected-(U2-IO2_1-Pad24)") (class "Default")
      (node (ref "U2") (pin "24") (pinfunction "IO2_1_24") (pintype "bidirectional"))
    )
    (net (code "234") (name "unconnected-(U2-IO2_2-Pad25)") (class "Default")
      (node (ref "U2") (pin "25") (pinfunction "IO2_2_25") (pintype "bidirectional"))
    )
    (net (code "235") (name "unconnected-(U2-IO2_3-Pad26)") (class "Default")
      (node (ref "U2") (pin "26") (pinfunction "IO2_3_26") (pintype "bidirectional"))
    )
    (net (code "236") (name "unconnected-(U2-IO2_4-Pad31)") (class "Default")
      (node (ref "U2") (pin "31") (pinfunction "IO2_4_31") (pintype "bidirectional"))
    )
    (net (code "237") (name "unconnected-(U2-IO2_5-Pad32)") (class "Default")
      (node (ref "U2") (pin "32") (pinfunction "IO2_5_32") (pintype "bidirectional"))
    )
    (net (code "238") (name "unconnected-(U2-IO2_6-Pad33)") (class "Default")
      (node (ref "U2") (pin "33") (pinfunction "IO2_6_33") (pintype "bidirectional"))
    )
    (net (code "239") (name "unconnected-(U2-IO2_7-Pad35)") (class "Default")
      (node (ref "U2") (pin "35") (pinfunction "IO2_7_35") (pintype "bidirectional"))
    )
    (net (code "240") (name "unconnected-(U2-IO4_0-Pad45)") (class "Default")
      (node (ref "U2") (pin "45") (pinfunction "IO4_0_45") (pintype "bidirectional"))
    )
    (net (code "241") (name "unconnected-(U2-IO4_1-Pad47)") (class "Default")
      (node (ref "U2") (pin "47") (pinfunction "IO4_1_47") (pintype "bidirectional"))
    )
    (net (code "242") (name "unconnected-(U3-NC-Pad4)") (class "Default")
      (node (ref "U3") (pin "4") (pinfunction "NC_4") (pintype "no_connect"))
    )
    (net (code "243") (name "unconnected-(U6-1B-Pad1)") (class "Default")
      (node (ref "U6") (pin "1") (pinfunction "1B_1") (pintype "input"))
    )
    (net (code "244") (name "unconnected-(U6-1C-Pad18)") (class "Default")
      (node (ref "U6") (pin "18") (pinfunction "1C_18") (pintype "output"))
    )
    (net (code "245") (name "unconnected-(U6-2B-Pad2)") (class "Default")
      (node (ref "U6") (pin "2") (pinfunction "2B_2") (pintype "input"))
    )
    (net (code "246") (name "unconnected-(U6-2C-Pad17)") (class "Default")
      (node (ref "U6") (pin "17") (pinfunction "2C_17") (pintype "output"))
    )
    (net (code "247") (name "unconnected-(U9A-CHR0-Pad15)") (class "Default")
      (node (ref "U9") (pin "15") (pinfunction "CHR0_15") (pintype "output"))
    )
    (net (code "248") (name "unconnected-(U9A-CHR1-Pad14)") (class "Default")
      (node (ref "U9") (pin "14") (pinfunction "CHR1_14") (pintype "output"))
    )
    (net (code "249") (name "unconnected-(U9A-CHREN-Pad13)") (class "Default")
      (node (ref "U9") (pin "13") (pinfunction "CHREN_13") (pintype "output"))
    )
    (net (code "250") (name "unconnected-(U9A-CTS-Pad23)") (class "Default")
      (node (ref "U9") (pin "23") (pinfunction "CTS_23") (pintype "input"))
    )
    (net (code "251") (name "unconnected-(U9A-DCD-Pad1)") (class "Default")
      (node (ref "U9") (pin "1") (pinfunction "DCD_1") (pintype "input"))
    )
    (net (code "252") (name "unconnected-(U9A-DSR-Pad27)") (class "Default")
      (node (ref "U9") (pin "27") (pinfunction "DSR_27") (pintype "input"))
    )
    (net (code "253") (name "unconnected-(U9A-GPIO.2{slash}RS485-Pad17)") (class "Default")
      (node (ref "U9") (pin "17") (pinfunction "GPIO.2/RS485_17") (pintype "bidirectional"))
    )
    (net (code "254") (name "unconnected-(U9A-GPIO.3{slash}WAKEUP-Pad16)") (class "Default")
      (node (ref "U9") (pin "16") (pinfunction "GPIO.3/WAKEUP_16") (pintype "bidirectional"))
    )
    (net (code "255") (name "unconnected-(U9A-GPIO.4-Pad22)") (class "Default")
      (node (ref "U9") (pin "22") (pinfunction "GPIO.4_22") (pintype "bidirectional"))
    )
    (net (code "256") (name "unconnected-(U9A-GPIO.5-Pad21)") (class "Default")
      (node (ref "U9") (pin "21") (pinfunction "GPIO.5_21") (pintype "bidirectional"))
    )
    (net (code "257") (name "unconnected-(U9A-GPIO.6-Pad20)") (class "Default")
      (node (ref "U9") (pin "20") (pinfunction "GPIO.6_20") (pintype "bidirectional"))
    )
    (net (code "258") (name "unconnected-(U9A-RI{slash}CLK-Pad2)") (class "Default")
      (node (ref "U9") (pin "2") (pinfunction "RI/CLK_2") (pintype "bidirectional"))
    )
    (net (code "259") (name "unconnected-(U9A-SUSPEND-Pad12)") (class "Default")
      (node (ref "U9") (pin "12") (pinfunction "SUSPEND_12") (pintype "output"))
    )
    (net (code "260") (name "unconnected-(U9A-SUSPENDB-Pad11)") (class "Default")
      (node (ref "U9") (pin "11") (pinfunction "SUSPENDB_11") (pintype "output"))
    )
    (net (code "261") (name "unconnected-(U9B-NC-Pad10)") (class "Default")
      (node (ref "U9") (pin "10") (pinfunction "NC_10") (pintype "no_connect"))
    )
    (net (code "262") (name "unconnected-(U10-DNC-Pad4)") (class "Default")
      (node (ref "U10") (pin "4") (pinfunction "DNC_4") (pintype "no_connect"))
    )
    (net (code "263") (name "unconnected-(U10-DNC_2-Pad3)") (class "Default")
      (node (ref "U10") (pin "3") (pinfunction "DNC_2_3") (pintype "no_connect"))
    )
    (net (code "264") (name "unconnected-(U12-D1--Pad2)") (class "Default")
      (node (ref "U12") (pin "2") (pinfunction "D1-_2") (pintype "bidirectional"))
    )
    (net (code "265") (name "unconnected-(U12-NC_4-Pad9)") (class "Default")
      (node (ref "U12") (pin "9") (pinfunction "NC_4_9") (pintype "passive"))
    )
    (net (code "266") (name "unconnected-(U14-1B-Pad1)") (class "Default")
      (node (ref "U14") (pin "1") (pinfunction "1B_1") (pintype "input"))
    )
    (net (code "267") (name "unconnected-(U14-1C-Pad18)") (class "Default")
      (node (ref "U14") (pin "18") (pinfunction "1C_18") (pintype "output"))
    )
    (net (code "268") (name "unconnected-(U14-2B-Pad2)") (class "Default")
      (node (ref "U14") (pin "2") (pinfunction "2B_2") (pintype "input"))
    )
    (net (code "269") (name "unconnected-(U14-2C-Pad17)") (class "Default")
      (node (ref "U14") (pin "17") (pinfunction "2C_17") (pintype "output"))
    )
    (net (code "270") (name "unconnected-(U25-DNC-Pad5)") (class "Default")
      (node (ref "U25") (pin "5") (pinfunction "DNC_5") (pintype "passive"))
    )
    (net (code "271") (name "unconnected-(U25-DNC_2-Pad4)") (class "Default")
      (node (ref "U25") (pin "4") (pinfunction "DNC_2_4") (pintype "passive"))
    )
    (net (code "272") (name "unconnected-(U25-PGOOD-Pad6)") (class "Default")
      (node (ref "U25") (pin "6") (pinfunction "PGOOD_6") (pintype "passive"))
    )
    (net (code "273") (name "unconnected-(U25-V5V-Pad13)") (class "Default")
      (node (ref "U25") (pin "13") (pinfunction "V5V_13") (pintype "passive"))
    )
    (net (code "274") (name "unconnected-(U28-I032-Pad8)") (class "Default")
      (node (ref "U28") (pin "8") (pinfunction "I032_8") (pintype "bidirectional"))
    )
    (net (code "275") (name "unconnected-(U28-I033-Pad9)") (class "Default")
      (node (ref "U28") (pin "9") (pinfunction "I033_9") (pintype "bidirectional"))
    )
    (net (code "276") (name "unconnected-(U28-I034-Pad6)") (class "Default")
      (node (ref "U28") (pin "6") (pinfunction "I034_6") (pintype "input"))
    )
    (net (code "277") (name "unconnected-(U28-I035-Pad7)") (class "Default")
      (node (ref "U28") (pin "7") (pinfunction "I035_7") (pintype "input"))
    )
    (net (code "278") (name "unconnected-(U28-IO5-Pad29)") (class "Default")
      (node (ref "U28") (pin "29") (pinfunction "IO5_29") (pintype "bidirectional"))
    )
    (net (code "279") (name "unconnected-(U28-IO14-Pad13)") (class "Default")
      (node (ref "U28") (pin "13") (pinfunction "IO14_13") (pintype "bidirectional"))
    )
    (net (code "280") (name "unconnected-(U28-IO15-Pad23)") (class "Default")
      (node (ref "U28") (pin "23") (pinfunction "IO15_23") (pintype "bidirectional"))
    )
    (net (code "281") (name "unconnected-(U28-IO17-Pad28)") (class "Default")
      (node (ref "U28") (pin "28") (pinfunction "IO17_28") (pintype "bidirectional"))
    )
    (net (code "282") (name "unconnected-(U28-IO22-Pad36)") (class "Default")
      (node (ref "U28") (pin "36") (pinfunction "IO22_36") (pintype "bidirectional"))
    )
    (net (code "283") (name "unconnected-(U28-SCL{slash}CLK-Pad20)") (class "Default")
      (node (ref "U28") (pin "20") (pinfunction "SCL/CLK_20") (pintype "bidirectional"))
    )
    (net (code "284") (name "unconnected-(U28-SCS{slash}CMD-Pad19)") (class "Default")
      (node (ref "U28") (pin "19") (pinfunction "SCS/CMD_19") (pintype "bidirectional"))
    )
    (net (code "285") (name "unconnected-(U28-SD1{slash}SD1-Pad22)") (class "Default")
      (node (ref "U28") (pin "22") (pinfunction "SD1/SD1_22") (pintype "bidirectional"))
    )
    (net (code "286") (name "unconnected-(U28-SDO{slash}SD0-Pad21)") (class "Default")
      (node (ref "U28") (pin "21") (pinfunction "SDO/SD0_21") (pintype "bidirectional"))
    )
    (net (code "287") (name "unconnected-(U28-SENSOR_VN-Pad5)") (class "Default")
      (node (ref "U28") (pin "5") (pinfunction "SENSOR_VN_5") (pintype "input"))
    )
    (net (code "288") (name "unconnected-(U28-SENSOR_VP-Pad4)") (class "Default")
      (node (ref "U28") (pin "4") (pinfunction "SENSOR_VP_4") (pintype "input"))
    )
    (net (code "289") (name "unconnected-(U28-SHD{slash}SD2-Pad17)") (class "Default")
      (node (ref "U28") (pin "17") (pinfunction "SHD/SD2_17") (pintype "bidirectional"))
    )
    (net (code "290") (name "unconnected-(U28-SWP{slash}SD3-Pad18)") (class "Default")
      (node (ref "U28") (pin "18") (pinfunction "SWP/SD3_18") (pintype "bidirectional"))
    )
    (net (code "291") (name "unconnected-(U32-DO-Pad1)") (class "Default")
      (node (ref "U32") (pin "1") (pinfunction "DO_1") (pintype "output"))
    )
  )
)
